# RX_Board.net
KiCad netlist of a schematic drawn in Altium Designer
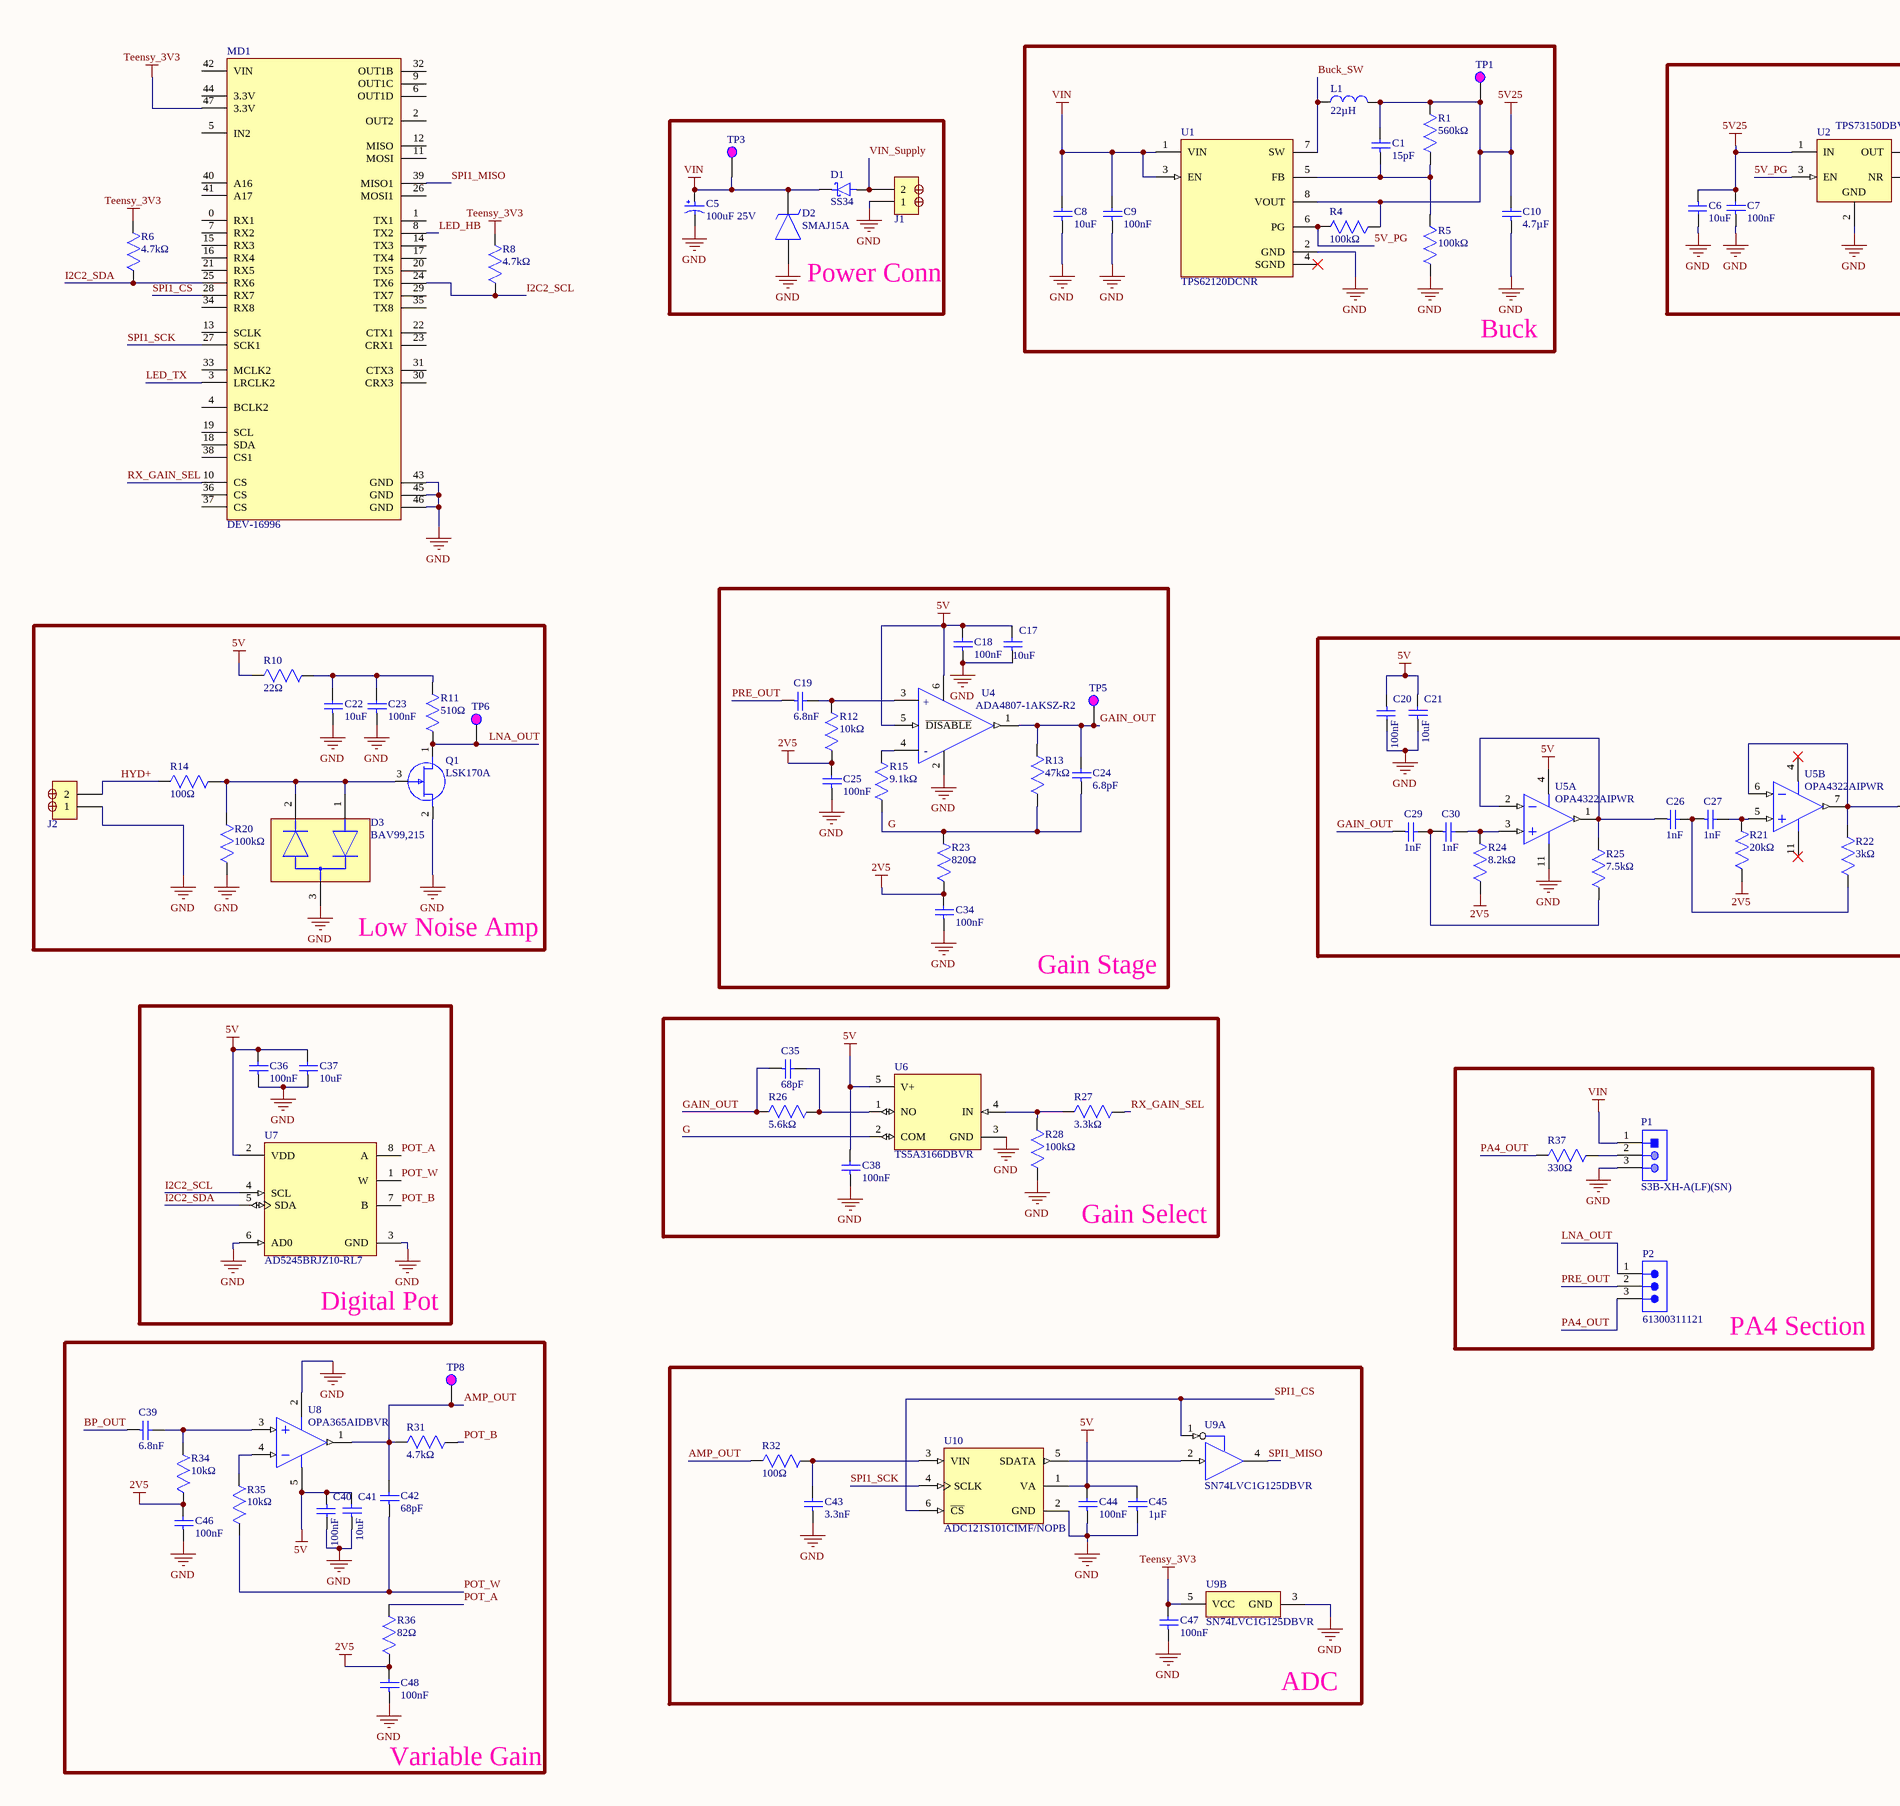
[diagram p0: RX_Board.SchDoc, left]
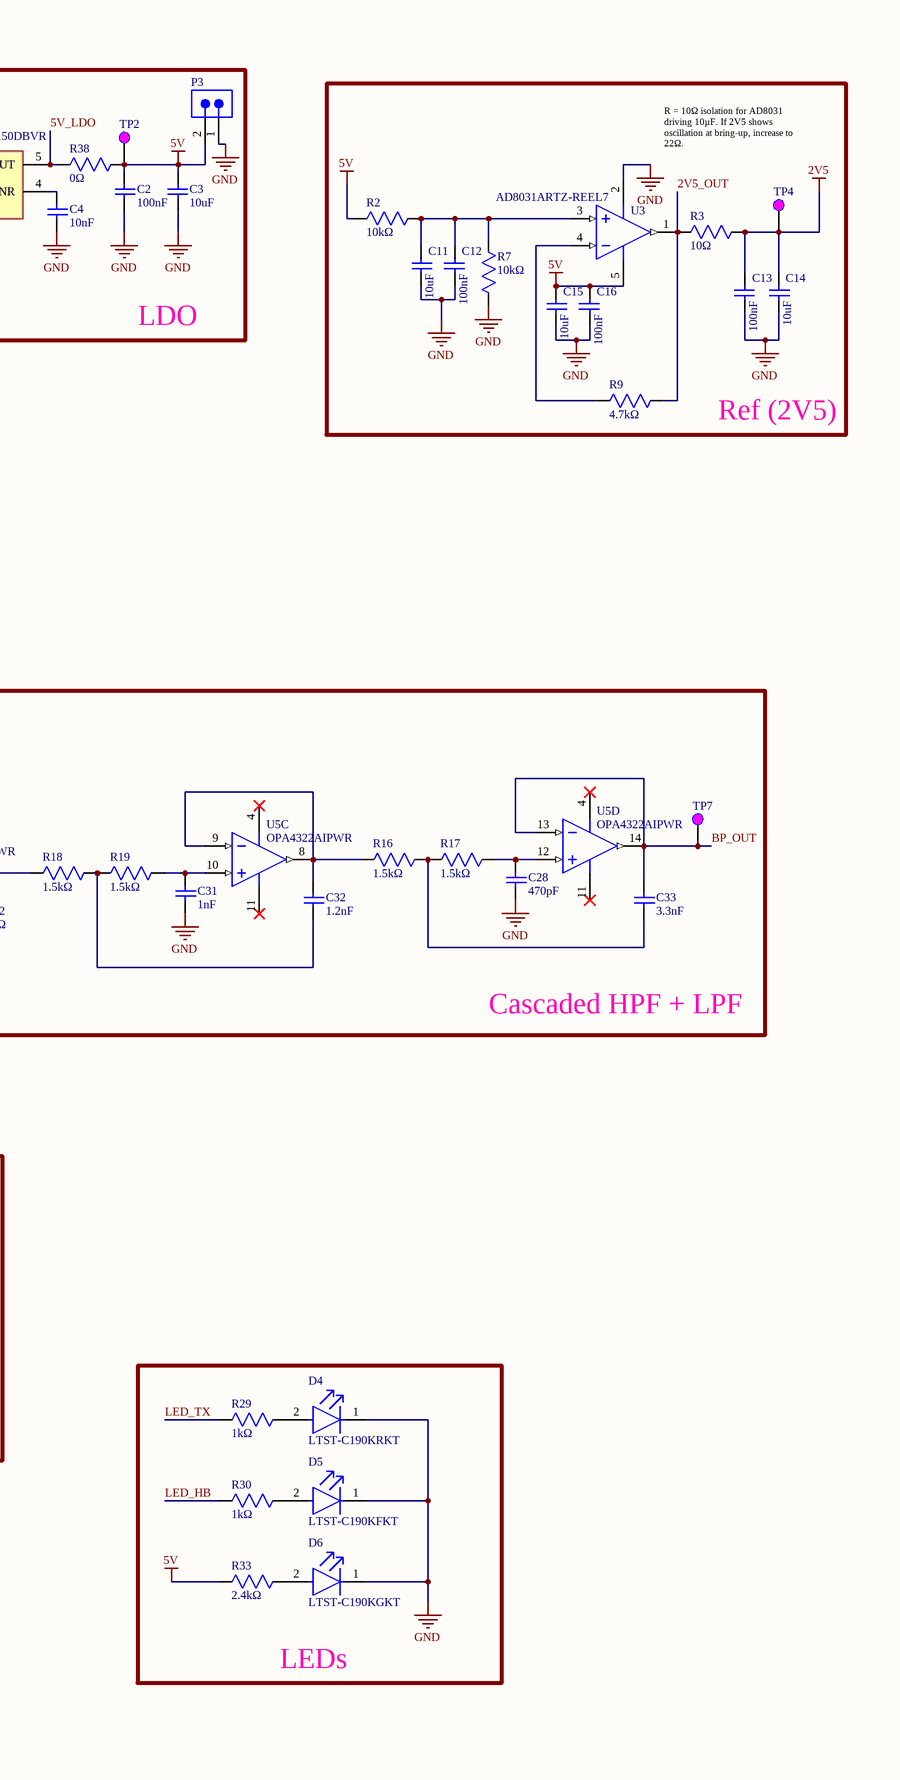
[diagram p1: RX_Board.SchDoc, right]

(export (version "E")
  (design (tool "Eeschema 10.0.6"))
  (components
    (comp (ref "C1")
      (value "15pF")
      (footprint "CAP_0603")
      (description "Multilayer Ceramic Capacitor, 15 pF, 50 V, ± 5%, C0G (NP0), 0603 [1608 Metric]")
      (fields
        (field (name "MANUFACTURER") "Samsung Electro-Mechanics")
        (field (name "MANUFACTURER PART NUMBER") "CL10C150JB8NNNC")
      )
      (libsource (lib "Custom_UAM_Parts") (part "CL10C150JB8NNNC"))
    )
    (comp (ref "C2")
      (value "100nF")
      (footprint "CAP_0603")
      (description "Multilayer Ceramic Capacitor, CC Series, 0.1 - F, - 10%, X7R, 50 V, 0603 [1608 Metric]")
      (fields
        (field (name "MANUFACTURER") "Yageo Group")
        (field (name "MANUFACTURER PART NUMBER") "CC0603KRX7R9BB104")
      )
      (libsource (lib "Custom_UAM_Parts") (part "CC0603KRX7R9BB104"))
    )
    (comp (ref "C3")
      (value "10uF")
      (footprint "CAP_0603")
      (description "25V 10uF X5R ±20% 0603 Multilayer Ceramic Capacitors MLCC - SMD/SMT ROHS")
      (fields
        (field (name "MANUFACTURER") "Samsung Electro-Mechanics")
        (field (name "MANUFACTURER PART NUMBER") "CL10A106MA8NRNC")
      )
      (libsource (lib "Custom_UAM_Parts") (part "CL10A106MA8NRNC"))
    )
    (comp (ref "C4")
      (value "10nF")
      (footprint "CAP_0603")
      (description "Surface Mount Ceramic Multilayer Capacitor 0.01uF 5% X7R 50V 0603 Paper T/R")
      (fields
        (field (name "MANUFACTURER") "Yageo Group")
        (field (name "MANUFACTURER PART NUMBER") "CC0603JRX7R9BB103")
      )
      (libsource (lib "Custom_UAM_Parts") (part "CC0603JRX7R9BB103"))
    )
    (comp (ref "C5")
      (value "100uF 25V")
      (footprint "SamacSys:CAPAE660X800N")
      (description "Capacitor Polarised")
      (fields
        (field (name "MANUFACTURER_PART_NUMBER") "RVT1E101M0607")
        (field (name "JLCPCB PART NUMBER") "C72477")
      )
      (libsource (lib "Custom_UAM_Parts") (part "RVT1E101M0607"))
    )
    (comp (ref "C6")
      (value "10uF")
      (footprint "CAP_0603")
      (description "25V 10uF X5R ±20% 0603 Multilayer Ceramic Capacitors MLCC - SMD/SMT ROHS")
      (fields
        (field (name "MANUFACTURER") "Samsung Electro-Mechanics")
        (field (name "MANUFACTURER PART NUMBER") "CL10A106MA8NRNC")
      )
      (libsource (lib "Custom_UAM_Parts") (part "CL10A106MA8NRNC"))
    )
    (comp (ref "C7")
      (value "100nF")
      (footprint "CAP_0603")
      (description "Multilayer Ceramic Capacitor, CC Series, 0.1 - F, - 10%, X7R, 50 V, 0603 [1608 Metric]")
      (fields
        (field (name "MANUFACTURER") "Yageo Group")
        (field (name "MANUFACTURER PART NUMBER") "CC0603KRX7R9BB104")
      )
      (libsource (lib "Custom_UAM_Parts") (part "CC0603KRX7R9BB104"))
    )
    (comp (ref "C8")
      (value "10uF")
      (footprint "CAP_0603")
      (description "25V 10uF X5R ±20% 0603 Multilayer Ceramic Capacitors MLCC - SMD/SMT ROHS")
      (fields
        (field (name "MANUFACTURER") "Samsung Electro-Mechanics")
        (field (name "MANUFACTURER PART NUMBER") "CL10A106MA8NRNC")
      )
      (libsource (lib "Custom_UAM_Parts") (part "CL10A106MA8NRNC"))
    )
    (comp (ref "C9")
      (value "100nF")
      (footprint "CAP_0603")
      (description "Multilayer Ceramic Capacitor, CC Series, 0.1 - F, - 10%, X7R, 50 V, 0603 [1608 Metric]")
      (fields
        (field (name "MANUFACTURER") "Yageo Group")
        (field (name "MANUFACTURER PART NUMBER") "CC0603KRX7R9BB104")
      )
      (libsource (lib "Custom_UAM_Parts") (part "CC0603KRX7R9BB104"))
    )
    (comp (ref "C10")
      (value "4.7µF")
      (footprint "CAP_0603")
      (description "25V 4.7uF X5R 卤10% 0603 Multilayer Ceramic Capacitors MLCC - SMD/SMT ROHS")
      (fields
        (field (name "MANUFACTURER") "Samsung Electro-Mechanics")
        (field (name "MANUFACTURER PART NUMBER") "CL10A475KA8NQNC")
      )
      (libsource (lib "Custom_UAM_Parts") (part "CL10A475KA8NQNC"))
    )
    (comp (ref "C11")
      (value "10uF")
      (footprint "CAP_0603")
      (description "25V 10uF X5R ±20% 0603 Multilayer Ceramic Capacitors MLCC - SMD/SMT ROHS")
      (fields
        (field (name "MANUFACTURER") "Samsung Electro-Mechanics")
        (field (name "MANUFACTURER PART NUMBER") "CL10A106MA8NRNC")
      )
      (libsource (lib "Custom_UAM_Parts") (part "CL10A106MA8NRNC"))
    )
    (comp (ref "C12")
      (value "100nF")
      (footprint "CAP_0603")
      (description "Multilayer Ceramic Capacitor, CC Series, 0.1 - F, - 10%, X7R, 50 V, 0603 [1608 Metric]")
      (fields
        (field (name "MANUFACTURER") "Yageo Group")
        (field (name "MANUFACTURER PART NUMBER") "CC0603KRX7R9BB104")
      )
      (libsource (lib "Custom_UAM_Parts") (part "CC0603KRX7R9BB104"))
    )
    (comp (ref "C13")
      (value "100nF")
      (footprint "CAP_0603")
      (description "Multilayer Ceramic Capacitor, CC Series, 0.1 - F, - 10%, X7R, 50 V, 0603 [1608 Metric]")
      (fields
        (field (name "MANUFACTURER") "Yageo Group")
        (field (name "MANUFACTURER PART NUMBER") "CC0603KRX7R9BB104")
      )
      (libsource (lib "Custom_UAM_Parts") (part "CC0603KRX7R9BB104"))
    )
    (comp (ref "C14")
      (value "10uF")
      (footprint "CAP_0603")
      (description "25V 10uF X5R ±20% 0603 Multilayer Ceramic Capacitors MLCC - SMD/SMT ROHS")
      (fields
        (field (name "MANUFACTURER") "Samsung Electro-Mechanics")
        (field (name "MANUFACTURER PART NUMBER") "CL10A106MA8NRNC")
      )
      (libsource (lib "Custom_UAM_Parts") (part "CL10A106MA8NRNC"))
    )
    (comp (ref "C15")
      (value "10uF")
      (footprint "CAP_0603")
      (description "25V 10uF X5R ±20% 0603 Multilayer Ceramic Capacitors MLCC - SMD/SMT ROHS")
      (fields
        (field (name "MANUFACTURER") "Samsung Electro-Mechanics")
        (field (name "MANUFACTURER PART NUMBER") "CL10A106MA8NRNC")
      )
      (libsource (lib "Custom_UAM_Parts") (part "CL10A106MA8NRNC"))
    )
    (comp (ref "C16")
      (value "100nF")
      (footprint "CAP_0603")
      (description "Multilayer Ceramic Capacitor, CC Series, 0.1 - F, - 10%, X7R, 50 V, 0603 [1608 Metric]")
      (fields
        (field (name "MANUFACTURER") "Yageo Group")
        (field (name "MANUFACTURER PART NUMBER") "CC0603KRX7R9BB104")
      )
      (libsource (lib "Custom_UAM_Parts") (part "CC0603KRX7R9BB104"))
    )
    (comp (ref "C17")
      (value "10uF")
      (footprint "CAP_0603")
      (description "25V 10uF X5R ±20% 0603 Multilayer Ceramic Capacitors MLCC - SMD/SMT ROHS")
      (fields
        (field (name "MANUFACTURER") "Samsung Electro-Mechanics")
        (field (name "MANUFACTURER PART NUMBER") "CL10A106MA8NRNC")
      )
      (libsource (lib "Custom_UAM_Parts") (part "CL10A106MA8NRNC"))
    )
    (comp (ref "C18")
      (value "100nF")
      (footprint "CAP_0603")
      (description "Multilayer Ceramic Capacitor, CC Series, 0.1 - F, - 10%, X7R, 50 V, 0603 [1608 Metric]")
      (fields
        (field (name "MANUFACTURER") "Yageo Group")
        (field (name "MANUFACTURER PART NUMBER") "CC0603KRX7R9BB104")
      )
      (libsource (lib "Custom_UAM_Parts") (part "CC0603KRX7R9BB104"))
    )
    (comp (ref "C19")
      (value "6.8nF")
      (footprint "CAP_0603")
      (description "Surface Mount Ceramic Multilayer Capacitor 0.0068uF 10% X7R 50V 0603 Paper T/R")
      (fields
        (field (name "MANUFACTURER") "Yageo Group")
        (field (name "MANUFACTURER PART NUMBER") "CC0603KRX7R9BB682")
      )
      (libsource (lib "Custom_UAM_Parts") (part "CC0603KRX7R9BB682"))
    )
    (comp (ref "C20")
      (value "100nF")
      (footprint "CAP_0603")
      (description "Multilayer Ceramic Capacitor, CC Series, 0.1 - F, - 10%, X7R, 50 V, 0603 [1608 Metric]")
      (fields
        (field (name "MANUFACTURER") "Yageo Group")
        (field (name "MANUFACTURER PART NUMBER") "CC0603KRX7R9BB104")
      )
      (libsource (lib "Custom_UAM_Parts") (part "CC0603KRX7R9BB104"))
    )
    (comp (ref "C21")
      (value "10uF")
      (footprint "CAP_0603")
      (description "25V 10uF X5R ±20% 0603 Multilayer Ceramic Capacitors MLCC - SMD/SMT ROHS")
      (fields
        (field (name "MANUFACTURER") "Samsung Electro-Mechanics")
        (field (name "MANUFACTURER PART NUMBER") "CL10A106MA8NRNC")
      )
      (libsource (lib "Custom_UAM_Parts") (part "CL10A106MA8NRNC"))
    )
    (comp (ref "C22")
      (value "10uF")
      (footprint "CAP_0603")
      (description "25V 10uF X5R ±20% 0603 Multilayer Ceramic Capacitors MLCC - SMD/SMT ROHS")
      (fields
        (field (name "MANUFACTURER") "Samsung Electro-Mechanics")
        (field (name "MANUFACTURER PART NUMBER") "CL10A106MA8NRNC")
      )
      (libsource (lib "Custom_UAM_Parts") (part "CL10A106MA8NRNC"))
    )
    (comp (ref "C23")
      (value "100nF")
      (footprint "CAP_0603")
      (description "Multilayer Ceramic Capacitor, CC Series, 0.1 - F, - 10%, X7R, 50 V, 0603 [1608 Metric]")
      (fields
        (field (name "MANUFACTURER") "Yageo Group")
        (field (name "MANUFACTURER PART NUMBER") "CC0603KRX7R9BB104")
      )
      (libsource (lib "Custom_UAM_Parts") (part "CC0603KRX7R9BB104"))
    )
    (comp (ref "C24")
      (value "6.8pF")
      (footprint "CAP_0603")
      (description "Surface Mount Ceramic Multilayer Capacitor 6.8pF 0.25pF C0G 50V 0603 Paper T/R")
      (fields
        (field (name "MANUFACTURER") "Yageo Group")
        (field (name "MANUFACTURER PART NUMBER") "CC0603CRNPO9BN6R8")
      )
      (libsource (lib "Custom_UAM_Parts") (part "CC0603CRNPO9BN6R8"))
    )
    (comp (ref "C25")
      (value "100nF")
      (footprint "CAP_0603")
      (description "Multilayer Ceramic Capacitor, CC Series, 0.1 - F, - 10%, X7R, 50 V, 0603 [1608 Metric]")
      (fields
        (field (name "MANUFACTURER") "Yageo Group")
        (field (name "MANUFACTURER PART NUMBER") "CC0603KRX7R9BB104")
      )
      (libsource (lib "Custom_UAM_Parts") (part "CC0603KRX7R9BB104"))
    )
    (comp (ref "C26")
      (value "1nF")
      (footprint "CAP_0603")
      (description "50V 1nF NP0 ±5% 0603 Multilayer Ceramic Capacitors MLCC - SMD/SMT ROHS")
      (fields
        (field (name "MANUFACTURER") "Yageo Group")
        (field (name "MANUFACTURER PART NUMBER") "CC0603JRNPO9BN102")
      )
      (libsource (lib "Custom_UAM_Parts") (part "CC0603JRNPO9BN102"))
    )
    (comp (ref "C27")
      (value "1nF")
      (footprint "CAP_0603")
      (description "50V 1nF NP0 ±5% 0603 Multilayer Ceramic Capacitors MLCC - SMD/SMT ROHS")
      (fields
        (field (name "MANUFACTURER") "Yageo Group")
        (field (name "MANUFACTURER PART NUMBER") "CC0603JRNPO9BN102")
      )
      (libsource (lib "Custom_UAM_Parts") (part "CC0603JRNPO9BN102"))
    )
    (comp (ref "C28")
      (value "470pF")
      (footprint "CAP_0603")
      (description "50V 470pF NP0 ±1% 0603 Multilayer Ceramic Capacitors MLCC - SMD/SMT ROHS")
      (fields
        (field (name "MANUFACTURER") "Yageo Group")
        (field (name "MANUFACTURER PART NUMBER") "CC0603FRNPO9BN471")
      )
      (libsource (lib "Custom_UAM_Parts") (part "CC0603FRNPO9BN471"))
    )
    (comp (ref "C29")
      (value "1nF")
      (footprint "CAP_0603")
      (description "50V 1nF NP0 ±5% 0603 Multilayer Ceramic Capacitors MLCC - SMD/SMT ROHS")
      (fields
        (field (name "MANUFACTURER") "Yageo Group")
        (field (name "MANUFACTURER PART NUMBER") "CC0603JRNPO9BN102")
      )
      (libsource (lib "Custom_UAM_Parts") (part "CC0603JRNPO9BN102"))
    )
    (comp (ref "C30")
      (value "1nF")
      (footprint "CAP_0603")
      (description "50V 1nF NP0 ±5% 0603 Multilayer Ceramic Capacitors MLCC - SMD/SMT ROHS")
      (fields
        (field (name "MANUFACTURER") "Yageo Group")
        (field (name "MANUFACTURER PART NUMBER") "CC0603JRNPO9BN102")
      )
      (libsource (lib "Custom_UAM_Parts") (part "CC0603JRNPO9BN102"))
    )
    (comp (ref "C31")
      (value "1nF")
      (footprint "CAP_0603")
      (description "50V 1nF NP0 ±5% 0603 Multilayer Ceramic Capacitors MLCC - SMD/SMT ROHS")
      (fields
        (field (name "MANUFACTURER") "Yageo Group")
        (field (name "MANUFACTURER PART NUMBER") "CC0603JRNPO9BN102")
      )
      (libsource (lib "Custom_UAM_Parts") (part "CC0603JRNPO9BN102"))
    )
    (comp (ref "C32")
      (value "1.2nF")
      (footprint "CAP_0603")
      (description "50V 1.2nF NP0 ±5% 0603 Multilayer Ceramic Capacitors MLCC - SMD/SMT ROHS")
      (fields
        (field (name "MANUFACTURER") "Yageo Group")
        (field (name "MANUFACTURER PART NUMBER") "CC0603JRNPO9BN122")
      )
      (libsource (lib "Custom_UAM_Parts") (part "CC0603JRNPO9BN122"))
    )
    (comp (ref "C33")
      (value "3.3nF")
      (footprint "CAP_0603")
      (description "50V 3.3nF NP0 ±5% 0603 Multilayer Ceramic Capacitors MLCC - SMD/SMT ROHS")
      (fields
        (field (name "MANUFACTURER") "Yageo Group")
        (field (name "MANUFACTURER PART NUMBER") "CC0603JRNPO9BN332")
      )
      (libsource (lib "Custom_UAM_Parts") (part "CC0603JRNPO9BN332"))
    )
    (comp (ref "C34")
      (value "100nF")
      (footprint "CAP_0603")
      (description "Multilayer Ceramic Capacitor, CC Series, 0.1 - F, - 10%, X7R, 50 V, 0603 [1608 Metric]")
      (fields
        (field (name "MANUFACTURER") "Yageo Group")
        (field (name "MANUFACTURER PART NUMBER") "CC0603KRX7R9BB104")
      )
      (libsource (lib "Custom_UAM_Parts") (part "CC0603KRX7R9BB104"))
    )
    (comp (ref "C35")
      (value "68pF")
      (footprint "CAP_0603")
      (description "Multilayer Ceramic Capacitor, 68 pF, 50 V, ± 5%, C0G (NP0), 0603 [1608 Metric]")
      (fields
        (field (name "MANUFACTURER") "Yageo Group")
        (field (name "MANUFACTURER PART NUMBER") "CC0603JRNPO9BN680")
      )
      (libsource (lib "Custom_UAM_Parts") (part "CC0603JRNPO9BN680"))
    )
    (comp (ref "C36")
      (value "100nF")
      (footprint "CAP_0603")
      (description "Multilayer Ceramic Capacitor, CC Series, 0.1 - F, - 10%, X7R, 50 V, 0603 [1608 Metric]")
      (fields
        (field (name "MANUFACTURER") "Yageo Group")
        (field (name "MANUFACTURER PART NUMBER") "CC0603KRX7R9BB104")
      )
      (libsource (lib "Custom_UAM_Parts") (part "CC0603KRX7R9BB104"))
    )
    (comp (ref "C37")
      (value "10uF")
      (footprint "CAP_0603")
      (description "25V 10uF X5R ±20% 0603 Multilayer Ceramic Capacitors MLCC - SMD/SMT ROHS")
      (fields
        (field (name "MANUFACTURER") "Samsung Electro-Mechanics")
        (field (name "MANUFACTURER PART NUMBER") "CL10A106MA8NRNC")
      )
      (libsource (lib "Custom_UAM_Parts") (part "CL10A106MA8NRNC"))
    )
    (comp (ref "C38")
      (value "100nF")
      (footprint "CAP_0603")
      (description "Multilayer Ceramic Capacitor, CC Series, 0.1 - F, - 10%, X7R, 50 V, 0603 [1608 Metric]")
      (fields
        (field (name "MANUFACTURER") "Yageo Group")
        (field (name "MANUFACTURER PART NUMBER") "CC0603KRX7R9BB104")
      )
      (libsource (lib "Custom_UAM_Parts") (part "CC0603KRX7R9BB104"))
    )
    (comp (ref "C39")
      (value "6.8nF")
      (footprint "CAP_0603")
      (description "Surface Mount Ceramic Multilayer Capacitor 0.0068uF 10% X7R 50V 0603 Paper T/R")
      (fields
        (field (name "MANUFACTURER") "Yageo Group")
        (field (name "MANUFACTURER PART NUMBER") "CC0603KRX7R9BB682")
      )
      (libsource (lib "Custom_UAM_Parts") (part "CC0603KRX7R9BB682"))
    )
    (comp (ref "C40")
      (value "100nF")
      (footprint "CAP_0603")
      (description "Multilayer Ceramic Capacitor, CC Series, 0.1 - F, - 10%, X7R, 50 V, 0603 [1608 Metric]")
      (fields
        (field (name "MANUFACTURER") "Yageo Group")
        (field (name "MANUFACTURER PART NUMBER") "CC0603KRX7R9BB104")
      )
      (libsource (lib "Custom_UAM_Parts") (part "CC0603KRX7R9BB104"))
    )
    (comp (ref "C41")
      (value "10uF")
      (footprint "CAP_0603")
      (description "25V 10uF X5R ±20% 0603 Multilayer Ceramic Capacitors MLCC - SMD/SMT ROHS")
      (fields
        (field (name "MANUFACTURER") "Samsung Electro-Mechanics")
        (field (name "MANUFACTURER PART NUMBER") "CL10A106MA8NRNC")
      )
      (libsource (lib "Custom_UAM_Parts") (part "CL10A106MA8NRNC"))
    )
    (comp (ref "C42")
      (value "68pF")
      (footprint "CAP_0603")
      (description "Multilayer Ceramic Capacitor, 68 pF, 50 V, ± 5%, C0G (NP0), 0603 [1608 Metric]")
      (fields
        (field (name "MANUFACTURER") "Yageo Group")
        (field (name "MANUFACTURER PART NUMBER") "CC0603JRNPO9BN680")
      )
      (libsource (lib "Custom_UAM_Parts") (part "CC0603JRNPO9BN680"))
    )
    (comp (ref "C43")
      (value "3.3nF")
      (footprint "CAP_0603")
      (description "50V 3.3nF NP0 ±5% 0603 Multilayer Ceramic Capacitors MLCC - SMD/SMT ROHS")
      (fields
        (field (name "MANUFACTURER") "Yageo Group")
        (field (name "MANUFACTURER PART NUMBER") "CC0603JRNPO9BN332")
      )
      (libsource (lib "Custom_UAM_Parts") (part "CC0603JRNPO9BN332"))
    )
    (comp (ref "C44")
      (value "100nF")
      (footprint "CAP_0603")
      (description "Multilayer Ceramic Capacitor, CC Series, 0.1 - F, - 10%, X7R, 50 V, 0603 [1608 Metric]")
      (fields
        (field (name "MANUFACTURER") "Yageo Group")
        (field (name "MANUFACTURER PART NUMBER") "CC0603KRX7R9BB104")
      )
      (libsource (lib "Custom_UAM_Parts") (part "CC0603KRX7R9BB104"))
    )
    (comp (ref "C45")
      (value "1µF")
      (footprint "CAP_0603")
      (description "MLCC - 0603 50 V X7R 1 uF 10 % Multilayer Ceramic Capacitor")
      (fields
        (field (name "MANUFACTURER") "Samsung Electro-Mechanics")
        (field (name "MANUFACTURER PART NUMBER") "CL10B105KB8NQNC")
      )
      (libsource (lib "Custom_UAM_Parts") (part "CL10B105KB8NQNC"))
    )
    (comp (ref "C46")
      (value "100nF")
      (footprint "CAP_0603")
      (description "Multilayer Ceramic Capacitor, CC Series, 0.1 - F, - 10%, X7R, 50 V, 0603 [1608 Metric]")
      (fields
        (field (name "MANUFACTURER") "Yageo Group")
        (field (name "MANUFACTURER PART NUMBER") "CC0603KRX7R9BB104")
      )
      (libsource (lib "Custom_UAM_Parts") (part "CC0603KRX7R9BB104"))
    )
    (comp (ref "C47")
      (value "100nF")
      (footprint "CAP_0603")
      (description "Multilayer Ceramic Capacitor, CC Series, 0.1 - F, - 10%, X7R, 50 V, 0603 [1608 Metric]")
      (fields
        (field (name "MANUFACTURER") "Yageo Group")
        (field (name "MANUFACTURER PART NUMBER") "CC0603KRX7R9BB104")
      )
      (libsource (lib "Custom_UAM_Parts") (part "CC0603KRX7R9BB104"))
    )
    (comp (ref "C48")
      (value "100nF")
      (footprint "CAP_0603")
      (description "Multilayer Ceramic Capacitor, CC Series, 0.1 - F, - 10%, X7R, 50 V, 0603 [1608 Metric]")
      (fields
        (field (name "MANUFACTURER") "Yageo Group")
        (field (name "MANUFACTURER PART NUMBER") "CC0603KRX7R9BB104")
      )
      (libsource (lib "Custom_UAM_Parts") (part "CC0603KRX7R9BB104"))
    )
    (comp (ref "D1")
      (value "SS34")
      (footprint "SS34")
      (description "-55℃~+125℃ 3A 40V 500uA@40V 550mV@3A Independent SMA(DO-214AC) Schottky Diodes ROHS")
      (fields (field (name "MANUFACTURER") "MDD") (field (name "JLCPCB PART NUMBER") "C8678"))
      (libsource (lib "Custom_UAM_Parts") (part "SS34"))
    )
    (comp (ref "D2")
      (value "SMAJ15A")
      (footprint "DIOM5026X229N")
      (description "SMAJ Series 24.4 V 400 W Surface Mount Uni-Directional TVS Diode - DO-214AC")
      (fields (field (name "MANUFACTURER") "Littelfuse") (field (name "JLCPCB PART NUMBER") "C148216"))
      (libsource (lib "Custom_UAM_Parts") (part "SMAJ15A"))
    )
    (comp (ref "D3")
      (value "BAV99,215")
      (footprint "FP-SOT23-MFG")
      (description "DIODE ARRAY GP 100V 215MA SOT23")
      (fields (field (name "JLCPCB PART NUMBER") "C2500"))
      (libsource (lib "Altium Content Vault") (part "86a7eb6839269cc1691df5cbdd99f75"))
    )
    (comp (ref "D4")
      (value "LTST-C190KRKT")
      (footprint "FP-LTST-C190KRKT-MFG")
      (description "LED RED CLEAR CHIP SMD")
      (fields (field (name "JLCPCB PART NUMBER") "C94869"))
      (libsource (lib "Altium Content Vault") (part "8706943c75ba83719d021d2fdc84c58"))
    )
    (comp (ref "D5")
      (value "LTST-C190KFKT")
      (footprint "FP-LTST-C190KFKT-MFG")
      (description "LED ORANGE CLEAR CHIP SMD")
      (fields (field (name "JLCPCB PART NUMBER") "C157740"))
      (libsource (lib "Altium Content Vault") (part "8706943c75ba83719d021d2fdc84c58"))
    )
    (comp (ref "D6")
      (value "LTST-C190KGKT")
      (footprint "FP-LTST-C190KGKT-MFG")
      (description "LED GREEN CLEAR CHIP SMD")
      (fields (field (name "JLCPCB PART NUMBER") "C125094"))
      (libsource (lib "Altium Content Vault") (part "8706943c75ba83719d021d2fdc84c58"))
    )
    (comp (ref "J1")
      (value "DB301V-3.5-2P-GN-S")
      (footprint "DB301V-3.5-2P-GN-S")
      (fields (field (name "JLCPCB PART NUMBER") "C695629"))
      (libsource (lib "") (part "DB301V-3.5-2P-GN-S_1"))
    )
    (comp (ref "J2")
      (value "DB301V-3.5-2P-GN-S")
      (footprint "DB301V-3.5-2P-GN-S")
      (fields (field (name "JLCPCB PART NUMBER") "C695629"))
      (libsource (lib "Custom_UAM_Parts") (part "DB301V-3.5-2P-GN-S"))
    )
    (comp (ref "L1")
      (value "22µH")
      (footprint "SWPA5040S100MT")
      (description "General Purpose Inductor, 22uH, 20%, 1 Element, Ferrite-Core, SMD, 2020")
      (fields
        (field (name "MANUFACTURER") "Sunlord")
        (field (name "MANUFACTURER PART NUMBER") "SWPA5040S220MT")
      )
      (libsource (lib "Custom_UAM_Parts") (part "SWPA5040S220MT"))
    )
    (comp (ref "MD1")
      (value "DEV-16996")
      (footprint "FP-DEV-16996-MFG")
      (description "TEENSY 4.1 (HEADERS)")
      (libsource (lib "Altium Content Vault") (part "080115a1ce54750370cf87ec145ee29"))
    )
    (comp (ref "P1")
      (value "S3B-XH-A(LF)(SN)")
      (footprint "JST-S3B-XH-A(LF)(SN)_V")
      (libsource (lib "Altium Content Vault") (part "CN-1P-M-R3"))
    )
    (comp (ref "P2")
      (value "61300311121")
      (footprint "61300311121")
      (description "THT Vertical Pin Header WR-PHD, Pitch 2.54 mm, Single Row, 3 pins")
      (libsource (lib "Altium Content Vault") (part "Header_Male_1R_03P"))
    )
    (comp (ref "P3")
      (value "61300211121")
      (footprint "61300211121")
      (description "THT Vertical Pin Header WR-PHD, Pitch 2.54 mm, Single Row, 2 pins")
      (libsource (lib "Altium Content Vault") (part "Header_Male_1R_02P"))
    )
    (comp (ref "Q1")
      (value "LSK170A")
      (footprint "SOT96P237X122-3N")
      (description "Jfet N-ch 40V 10MA SOT23-3")
      (fields
        (field (name "MANUFACTURER") "Linear Systems")
        (field (name "MANUFACTURER PART NUMBER") "LSK170A SOT-23 3L ROHS")
      )
      (libsource (lib "Custom_UAM_Parts") (part "LSK170A SOT-23 3L ROHS"))
    )
    (comp (ref "R1")
      (value "560kΩ")
      (footprint "RES_0603")
      (description "100mW Thin Film Resistor 75V ±25ppm/℃ ±0.1% 560kΩ 0603 Chip Resistor - Surface Mount ROHS")
      (fields
        (field (name "MANUFACTURER") "Yageo Group")
        (field (name "MANUFACTURER PART NUMBER") "RT0603BRD07560KL")
      )
      (libsource (lib "Custom_UAM_Parts") (part "RT0603BRD07560KL"))
    )
    (comp (ref "R2")
      (value "10kΩ")
      (footprint "RES_0603")
      (description "Res Thin Film 0603 10K Ohm 0.1% 1/10W ¦25ppm/¦C SMD Paper T/R")
      (fields
        (field (name "MANUFACTURER") "Yageo Group")
        (field (name "MANUFACTURER PART NUMBER") "RT0603BRD0710KL")
      )
      (libsource (lib "Custom_UAM_Parts") (part "RT0603BRD0710KL"))
    )
    (comp (ref "R3")
      (value "10Ω")
      (footprint "RES_0603")
      (description "Res Thick Film 0603 10 Ohm 1% 0.1W(1/10W) ±200ppm/C Pad SMD T/R")
      (fields
        (field (name "MANUFACTURER") "Royal Ohm")
        (field (name "MANUFACTURER PART NUMBER") "0603WAF100JT5E")
      )
      (libsource (lib "Custom_UAM_Parts") (part "0603WAF100JT5E"))
    )
    (comp (ref "R4")
      (value "100kΩ")
      (footprint "RES_0603")
      (description "100mW Thin Film Resistor 75V ±25ppm/℃ ±0.1% 100kΩ 0603 Chip Resistor - Surface Mount ROHS")
      (fields
        (field (name "MANUFACTURER") "Yageo Group")
        (field (name "MANUFACTURER PART NUMBER") "RT0603BRD07100KL")
      )
      (libsource (lib "Custom_UAM_Parts") (part "RT0603BRD07100KL"))
    )
    (comp (ref "R5")
      (value "100kΩ")
      (footprint "RES_0603")
      (description "100mW Thin Film Resistor 75V ±25ppm/℃ ±0.1% 100kΩ 0603 Chip Resistor - Surface Mount ROHS")
      (fields
        (field (name "MANUFACTURER") "Yageo Group")
        (field (name "MANUFACTURER PART NUMBER") "RT0603BRD07100KL")
      )
      (libsource (lib "Custom_UAM_Parts") (part "RT0603BRD07100KL"))
    )
    (comp (ref "R6")
      (value "4.7kΩ")
      (footprint "RES_0603")
      (description "Yageo RC0603FR-074K7L Resistor 0603 SMD 4.7k Ohm 1% 100mW Thick Film")
      (fields
        (field (name "MANUFACTURER") "Yageo Group")
        (field (name "MANUFACTURER PART NUMBER") "RC0603FR-074K7L")
      )
      (libsource (lib "Custom_UAM_Parts") (part "RC0603FR-074K7L"))
    )
    (comp (ref "R7")
      (value "10kΩ")
      (footprint "RES_0603")
      (description "Res Thin Film 0603 10K Ohm 0.1% 1/10W ¦25ppm/¦C SMD Paper T/R")
      (fields
        (field (name "MANUFACTURER") "Yageo Group")
        (field (name "MANUFACTURER PART NUMBER") "RT0603BRD0710KL")
      )
      (libsource (lib "Custom_UAM_Parts") (part "RT0603BRD0710KL"))
    )
    (comp (ref "R8")
      (value "4.7kΩ")
      (footprint "RES_0603")
      (description "Yageo RC0603FR-074K7L Resistor 0603 SMD 4.7k Ohm 1% 100mW Thick Film")
      (fields
        (field (name "MANUFACTURER") "Yageo Group")
        (field (name "MANUFACTURER PART NUMBER") "RC0603FR-074K7L")
      )
      (libsource (lib "Custom_UAM_Parts") (part "RC0603FR-074K7L"))
    )
    (comp (ref "R9")
      (value "4.7kΩ")
      (footprint "RES_0603")
      (description "Yageo RC0603FR-074K7L Resistor 0603 SMD 4.7k Ohm 1% 100mW Thick Film")
      (fields
        (field (name "MANUFACTURER") "Yageo Group")
        (field (name "MANUFACTURER PART NUMBER") "RC0603FR-074K7L")
      )
      (libsource (lib "Custom_UAM_Parts") (part "RC0603FR-074K7L"))
    )
    (comp (ref "R10")
      (value "22Ω")
      (footprint "RES_0603")
      (description "Thick Film Resistors - SMD RMC 0603 1/10W 1% T/R-5000")
      (fields
        (field (name "MANUFACTURER") "Royal Ohm")
        (field (name "MANUFACTURER PART NUMBER") "0603WAF220JT5E")
      )
      (libsource (lib "Custom_UAM_Parts") (part "0603WAF220JT5E"))
    )
    (comp (ref "R11")
      (value "510Ω")
      (footprint "RES_0603")
      (description "Res Thick Film 0603 510 Ohm 1% 0.1W(1/10W) ±100ppm/C Pad SMD T/R")
      (fields
        (field (name "MANUFACTURER") "Royal Ohm")
        (field (name "MANUFACTURER PART NUMBER") "0603WAF5100T5E")
      )
      (libsource (lib "Custom_UAM_Parts") (part "0603WAF5100T5E"))
    )
    (comp (ref "R12")
      (value "10kΩ")
      (footprint "RES_0603")
      (description "Res Thin Film 0603 10K Ohm 0.1% 1/10W ¦25ppm/¦C SMD Paper T/R")
      (fields
        (field (name "MANUFACTURER") "Yageo Group")
        (field (name "MANUFACTURER PART NUMBER") "RT0603BRD0710KL")
      )
      (libsource (lib "Custom_UAM_Parts") (part "RT0603BRD0710KL"))
    )
    (comp (ref "R13")
      (value "47kΩ")
      (footprint "RES_0603")
      (description "Res Thick Film 0603 47K Ohm 1% 0.1W(1/10W) ±100ppm/C Pad SMD T/R")
      (fields
        (field (name "MANUFACTURER") "Royal Ohm")
        (field (name "MANUFACTURER PART NUMBER") "0603WAF4702T5E")
      )
      (libsource (lib "Custom_UAM_Parts") (part "0603WAF4702T5E"))
    )
    (comp (ref "R14")
      (value "100Ω")
      (footprint "RES_0603")
      (description "Res Thick Film 0603 100 Ohm 1% 0.1W(1/10W) ±200ppm/C Pad SMD T/R")
      (fields
        (field (name "MANUFACTURER") "Royal Ohm")
        (field (name "MANUFACTURER PART NUMBER") "0603WAF1000T5E")
      )
      (libsource (lib "Custom_UAM_Parts") (part "0603WAF1000T5E"))
    )
    (comp (ref "R15")
      (value "9.1kΩ")
      (footprint "RES_0603")
      (description "100mW Thick Film Resistors 75V ±100ppm/℃ ±1% 9.1kΩ 0603 Chip Resistor - Surface Mount ROHS")
      (fields
        (field (name "MANUFACTURER") "Royal Ohm")
        (field (name "MANUFACTURER PART NUMBER") "0603WAF9101T5E")
      )
      (libsource (lib "Custom_UAM_Parts") (part "0603WAF9101T5E"))
    )
    (comp (ref "R16")
      (value "1.5kΩ")
      (footprint "RES_0603")
      (description "Res Thick Film 0603 1.5K Ohm 1% 0.1W(1/10W) ±100ppm/C Pad SMD T/R")
      (fields
        (field (name "MANUFACTURER") "Royal Ohm")
        (field (name "MANUFACTURER PART NUMBER") "0603WAF1501T5E")
      )
      (libsource (lib "Custom_UAM_Parts") (part "0603WAF1501T5E"))
    )
    (comp (ref "R17")
      (value "1.5kΩ")
      (footprint "RES_0603")
      (description "Res Thick Film 0603 1.5K Ohm 1% 0.1W(1/10W) ±100ppm/C Pad SMD T/R")
      (fields
        (field (name "MANUFACTURER") "Royal Ohm")
        (field (name "MANUFACTURER PART NUMBER") "0603WAF1501T5E")
      )
      (libsource (lib "Custom_UAM_Parts") (part "0603WAF1501T5E"))
    )
    (comp (ref "R18")
      (value "1.5kΩ")
      (footprint "RES_0603")
      (description "Res Thick Film 0603 1.5K Ohm 1% 0.1W(1/10W) ±100ppm/C Pad SMD T/R")
      (fields
        (field (name "MANUFACTURER") "Royal Ohm")
        (field (name "MANUFACTURER PART NUMBER") "0603WAF1501T5E")
      )
      (libsource (lib "Custom_UAM_Parts") (part "0603WAF1501T5E"))
    )
    (comp (ref "R19")
      (value "1.5kΩ")
      (footprint "RES_0603")
      (description "Res Thick Film 0603 1.5K Ohm 1% 0.1W(1/10W) ±100ppm/C Pad SMD T/R")
      (fields
        (field (name "MANUFACTURER") "Royal Ohm")
        (field (name "MANUFACTURER PART NUMBER") "0603WAF1501T5E")
      )
      (libsource (lib "Custom_UAM_Parts") (part "0603WAF1501T5E"))
    )
    (comp (ref "R20")
      (value "100kΩ")
      (footprint "RES_0603")
      (description "100mW Thin Film Resistor 75V ±25ppm/℃ ±0.1% 100kΩ 0603 Chip Resistor - Surface Mount ROHS")
      (fields
        (field (name "MANUFACTURER") "Yageo Group")
        (field (name "MANUFACTURER PART NUMBER") "RT0603BRD07100KL")
      )
      (libsource (lib "Custom_UAM_Parts") (part "RT0603BRD07100KL"))
    )
    (comp (ref "R21")
      (value "20kΩ")
      (footprint "RES_0603")
      (description "100mW Thick Film Resistors 75V ±100ppm/℃ ±1% 20kΩ 0603 Chip Resistor - Surface Mount ROHS")
      (fields
        (field (name "MANUFACTURER") "Royal Ohm")
        (field (name "MANUFACTURER PART NUMBER") "0603WAF2002T5E")
      )
      (libsource (lib "Custom_UAM_Parts") (part "0603WAF2002T5E"))
    )
    (comp (ref "R22")
      (value "3kΩ")
      (footprint "RES_0603")
      (description "Thick Film Resistors - SMD RMC 0603 1/10W 1% T/R-5000")
      (fields
        (field (name "MANUFACTURER") "Royal Ohm")
        (field (name "MANUFACTURER PART NUMBER") "0603WAF3001T5E")
      )
      (libsource (lib "Custom_UAM_Parts") (part "0603WAF3001T5E"))
    )
    (comp (ref "R23")
      (value "820Ω")
      (footprint "RES_0603")
      (description "Thick Film Resistors - SMD RMC 0603 1/10W 1% T/R-5000")
      (fields
        (field (name "MANUFACTURER") "Royal Ohm")
        (field (name "MANUFACTURER PART NUMBER") "0603WAF8200T5E")
      )
      (libsource (lib "Custom_UAM_Parts") (part "0603WAF8200T5E"))
    )
    (comp (ref "R24")
      (value "8.2kΩ")
      (footprint "RES_0603")
      (description "Res Thick Film 0603 8.2K Ohm 1% 0.1W(1/10W) ±100ppm/C Pad SMD T/R")
      (fields
        (field (name "MANUFACTURER") "Royal Ohm")
        (field (name "MANUFACTURER PART NUMBER") "0603WAF8201T5E")
      )
      (libsource (lib "Custom_UAM_Parts") (part "0603WAF8201T5E"))
    )
    (comp (ref "R25")
      (value "7.5kΩ")
      (footprint "RES_0603")
      (fields
        (field (name "MANUFACTURER") "Royal Ohm")
        (field (name "MANUFACTURER PART NUMBER") "0603WAF7501T5E")
        (field (name "TOLERANCE") "1%")
      )
      (libsource (lib "Custom_UAM_Parts") (part "0603WAF7501T5E"))
    )
    (comp (ref "R26")
      (value "5.6kΩ")
      (footprint "RES_0603")
      (description "Res Thick Film 0603 5.6K Ohm 1% 0.1W(1/10W) ±100ppm/C Pad SMD T/R")
      (fields
        (field (name "MANUFACTURER") "Royal Ohm")
        (field (name "MANUFACTURER PART NUMBER") "0603WAF5601T5E")
      )
      (libsource (lib "Custom_UAM_Parts") (part "0603WAF5601T5E"))
    )
    (comp (ref "R27")
      (value "3.3kΩ")
      (footprint "RES_0603")
      (fields
        (field (name "MANUFACTURER") "Royal Ohm")
        (field (name "MANUFACTURER PART NUMBER") "0603WAF3301T5E")
        (field (name "TOLERANCE") "1%")
      )
      (libsource (lib "Custom_UAM_Parts") (part "0603WAF3301T5E"))
    )
    (comp (ref "R28")
      (value "100kΩ")
      (footprint "RES_0603")
      (description "100mW Thin Film Resistor 75V ±25ppm/℃ ±0.1% 100kΩ 0603 Chip Resistor - Surface Mount ROHS")
      (fields
        (field (name "MANUFACTURER") "Yageo Group")
        (field (name "MANUFACTURER PART NUMBER") "RT0603BRD07100KL")
      )
      (libsource (lib "Custom_UAM_Parts") (part "RT0603BRD07100KL"))
    )
    (comp (ref "R29")
      (value "1kΩ")
      (footprint "RES_0603")
      (description "Res Thick Film 0603 1K Ohm 1% 0.1W(1/10W) ±100ppm/C Pad SMD T/R")
      (fields
        (field (name "MANUFACTURER") "Royal Ohm")
        (field (name "MANUFACTURER PART NUMBER") "0603WAF1001T5E")
      )
      (libsource (lib "Custom_UAM_Parts") (part "0603WAF1001T5E"))
    )
    (comp (ref "R30")
      (value "1kΩ")
      (footprint "RES_0603")
      (description "Res Thick Film 0603 1K Ohm 1% 0.1W(1/10W) ±100ppm/C Pad SMD T/R")
      (fields
        (field (name "MANUFACTURER") "Royal Ohm")
        (field (name "MANUFACTURER PART NUMBER") "0603WAF1001T5E")
      )
      (libsource (lib "Custom_UAM_Parts") (part "0603WAF1001T5E"))
    )
    (comp (ref "R31")
      (value "4.7kΩ")
      (footprint "RES_0603")
      (description "Yageo RC0603FR-074K7L Resistor 0603 SMD 4.7k Ohm 1% 100mW Thick Film")
      (fields
        (field (name "MANUFACTURER") "Yageo Group")
        (field (name "MANUFACTURER PART NUMBER") "RC0603FR-074K7L")
      )
      (libsource (lib "Custom_UAM_Parts") (part "RC0603FR-074K7L"))
    )
    (comp (ref "R32")
      (value "100Ω")
      (footprint "RES_0603")
      (description "Res Thick Film 0603 100 Ohm 1% 0.1W(1/10W) ±200ppm/C Pad SMD T/R")
      (fields
        (field (name "MANUFACTURER") "Royal Ohm")
        (field (name "MANUFACTURER PART NUMBER") "0603WAF1000T5E")
      )
      (libsource (lib "Custom_UAM_Parts") (part "0603WAF1000T5E"))
    )
    (comp (ref "R33")
      (value "2.4kΩ")
      (footprint "RES_0603")
      (description "100mW Thick Film Resistors 75V ±100ppm/℃ ±1% 2.4kΩ 0603 Chip Resistor - Surface Mount ROHS")
      (fields
        (field (name "MANUFACTURER") "Royal Ohm")
        (field (name "MANUFACTURER PART NUMBER") "0603WAF2401T5E")
      )
      (libsource (lib "Custom_UAM_Parts") (part "0603WAF2401T5E"))
    )
    (comp (ref "R34")
      (value "10kΩ")
      (footprint "RES_0603")
      (description "Res Thin Film 0603 10K Ohm 0.1% 1/10W ¦25ppm/¦C SMD Paper T/R")
      (fields
        (field (name "MANUFACTURER") "Yageo Group")
        (field (name "MANUFACTURER PART NUMBER") "RT0603BRD0710KL")
      )
      (libsource (lib "Custom_UAM_Parts") (part "RT0603BRD0710KL"))
    )
    (comp (ref "R35")
      (value "10kΩ")
      (footprint "RES_0603")
      (description "Res Thin Film 0603 10K Ohm 0.1% 1/10W ¦25ppm/¦C SMD Paper T/R")
      (fields
        (field (name "MANUFACTURER") "Yageo Group")
        (field (name "MANUFACTURER PART NUMBER") "RT0603BRD0710KL")
      )
      (libsource (lib "Custom_UAM_Parts") (part "RT0603BRD0710KL"))
    )
    (comp (ref "R36")
      (value "82Ω")
      (footprint "RES_0603")
      (description "SMD Chip Resistor, 82 Ohm, ± 1%, 100 mW, 0603 [1608 Metric], Thick Film, General Purpose")
      (fields
        (field (name "MANUFACTURER") "Yageo Group")
        (field (name "MANUFACTURER PART NUMBER") "RC0603FR-0782RL")
      )
      (libsource (lib "Custom_UAM_Parts") (part "RC0603FR-0782RL"))
    )
    (comp (ref "R37")
      (value "330Ω")
      (footprint "RES_0603")
      (fields
        (field (name "MANUFACTURER") "Royal Ohm")
        (field (name "MANUFACTURER PART NUMBER") "0603WAF3300T5E")
        (field (name "TOLERANCE") "1%")
      )
      (libsource (lib "Custom_UAM_Parts") (part "0603WAF3300T5E"))
    )
    (comp (ref "R38")
      (value "0Ω")
      (footprint "RES_0603")
      (description "Zero Ohm Resistor, Jumper, 0603 [1608 Metric], Thick Film, 100 mW, 1 A, Surface Mount")
      (fields
        (field (name "MANUFACTURER") "Yageo Group")
        (field (name "MANUFACTURER PART NUMBER") "RC0603FR-070RL")
      )
      (libsource (lib "Custom_UAM_Parts") (part "RC0603FR-070RL"))
    )
    (comp (ref "TP1")
      (value "Test Point")
      (footprint "Test Point")
      (libsource (lib "Custom_UAM_Parts") (part "Test Point"))
    )
    (comp (ref "TP2")
      (value "Test Point")
      (footprint "Test Point")
      (libsource (lib "Custom_UAM_Parts") (part "Test Point"))
    )
    (comp (ref "TP3")
      (value "Test Point")
      (footprint "Test Point")
      (libsource (lib "Custom_UAM_Parts") (part "Test Point"))
    )
    (comp (ref "TP4")
      (value "Test Point")
      (footprint "Test Point")
      (libsource (lib "Custom_UAM_Parts") (part "Test Point"))
    )
    (comp (ref "TP5")
      (value "Test Point")
      (footprint "Test Point")
      (libsource (lib "Custom_UAM_Parts") (part "Test Point"))
    )
    (comp (ref "TP6")
      (value "Test Point")
      (footprint "Test Point")
      (libsource (lib "Custom_UAM_Parts") (part "Test Point"))
    )
    (comp (ref "TP7")
      (value "Test Point")
      (footprint "Test Point")
      (libsource (lib "Custom_UAM_Parts") (part "Test Point"))
    )
    (comp (ref "TP8")
      (value "Test Point")
      (footprint "Test Point")
      (libsource (lib "Custom_UAM_Parts") (part "Test Point"))
    )
    (comp (ref "U1")
      (value "TPS62120DCNR")
      (footprint "FP-DCN0008A-MFG")
      (description "IC REG BUCK ADJ 75MA SOT23-8")
      (libsource (lib "Altium Content Vault") (part "14865cc4e84ea28e7204c9f8caa9625"))
    )
    (comp (ref "U2")
      (value "TPS73150DBVR")
      (footprint "DBV0005A_N")
      (fields (field (name "MANUFACTURER") "Texas Instruments"))
      (libsource (lib "Altium Content Vault") (part "TI-TPS79NXX-YYSOT5"))
    )
    (comp (ref "U3")
      (value "AD8031ARTZ-REEL7")
      (footprint "ADI-RJ-5_L")
      (fields (field (name "MANUFACTURER") "Analog Devices") (field (name "GENERIC PART NUMBER") "AD8031"))
      (libsource (lib "Altium Content Vault") (part "ADI-AD80XX-5"))
    )
    (comp (ref "U4")
      (value "ADA4807-1AKSZ-R2")
      (footprint "FP-KS-6-IPC_C")
      (description "IC OPAMP VFB 1 CIRCUIT SC70-6")
      (fields
        (field (name "MANUFACTURER") "Analog Devices")
        (field (name "OCTOPART") "https://octopart.com/ada4807-1aksz-r2-analog+devices-52932031")
      )
      (libsource (lib "Altium Content Vault") (part "4985ff539af837c5b5b6b47cd6c0464"))
    )
    (comp (ref "U5")
      (value "OPA4322AIPWR")
      (footprint "PW0014A_N")
      (fields (field (name "MANUFACTURER") "Texas Instruments"))
      (libsource (lib "Altium Content Vault") (part "TI-OPA16X4_4XXX-14"))
    )
    (comp (ref "U6")
      (value "TS5A3166DBVR")
      (footprint "FP-DBV0005A-MFG")
      (description "IC SWITCH SPST SOT23-5")
      (fields
        (field (name "MANUFACTURER") "Texas Instruments")
        (field (name "OCTOPART") "https://octopart.com/ts5a3166dbvr-texas+instruments-512330")
      )
      (libsource (lib "Altium Content Vault") (part "821cfbbac4e375bc87997324a3db2e8"))
    )
    (comp (ref "U7")
      (value "AD5245BRJZ10-RL7")
      (footprint "FP-RJ-8-IPC_B")
      (description "IC DGT POT 10KOHM 256TAP SOT23-8")
      (fields (field (name "TOLERANCE") "30%") (field (name "JLCPCB PART NUMBER") "C144256"))
      (libsource (lib "Altium Content Vault") (part "777f9caa62b19d2ac513b26aa3e00a4"))
    )
    (comp (ref "U8")
      (value "OPA365AIDBVR")
      (footprint "DBV0005A_N")
      (fields (field (name "MANUFACTURER") "Texas Instruments") (field (name "JLCPCB PART NUMBER") "C96626"))
      (libsource (lib "Altium Content Vault") (part "TI-OPA364_5DBV5"))
    )
    (comp (ref "U9")
      (value "SN74LVC1G125DBVR")
      (footprint "DBV0005A_M")
      (description "Single Bus Buffer Gate With 3-State Outputs, DBV0005A, LARGE T&R")
      (fields
        (field (name "GENERIC PART NUMBER") "SN74LVC1G125")
        (field (name "MANUFACTURER") "Texas Instruments")
      )
      (libsource (lib "Altium Content Vault") (part "TI-SN74AXXXX1X125-5"))
    )
    (comp (ref "U10")
      (value "ADC121S101CIMF/NOPB")
      (footprint "MF06A_N")
      (description "Single Channel, 0.5 to 1 MSPS, 12-Bit A/D Converter, 6-pin SOT-23, Pb-Free")
      (fields
        (field (name "MANUFACTURER") "National Semiconductor")
        (field (name "JLCPCB PART NUMBER") "C74860")
      )
      (libsource (lib "Altium Content Vault") (part "CON-ADC-ADC101S101CIMF"))
    )
  )
  (nets
    (net (code "1") (name "/2V5_OUT") (class "Default")
      (node (ref "R3") (pin "1") (pinfunction "1_1") (pintype "passive"))
      (node (ref "R9") (pin "2") (pinfunction "2_2") (pintype "passive"))
      (node (ref "U3") (pin "1") (pinfunction "VOUT_1") (pintype "output"))
    )
    (net (code "2") (name "/5V_LDO") (class "Default")
      (node (ref "R38") (pin "1") (pinfunction "1_1") (pintype "passive"))
      (node (ref "U2") (pin "5") (pinfunction "OUT_5") (pintype "power_in"))
    )
    (net (code "3") (name "/5V_PG") (class "Default")
      (node (ref "R4") (pin "2") (pinfunction "2_2") (pintype "passive"))
      (node (ref "U1") (pin "6") (pinfunction "PG_6") (pintype "open_collector"))
      (node (ref "U2") (pin "3") (pinfunction "EN_3") (pintype "input"))
    )
    (net (code "4") (name "/AMP_OUT") (class "Default")
      (node (ref "C42") (pin "2") (pinfunction "2_2") (pintype "passive"))
      (node (ref "R31") (pin "1") (pinfunction "1_1") (pintype "passive"))
      (node (ref "R32") (pin "1") (pinfunction "1_1") (pintype "passive"))
      (node (ref "TP8") (pin "1") (pinfunction "1_1") (pintype "passive"))
      (node (ref "U8") (pin "1") (pinfunction "VOUT_1") (pintype "output"))
    )
    (net (code "5") (name "/BP_OUT") (class "Default")
      (node (ref "C33") (pin "2") (pinfunction "2_2") (pintype "passive"))
      (node (ref "C39") (pin "1") (pinfunction "1_1") (pintype "passive"))
      (node (ref "TP7") (pin "1") (pinfunction "1_1") (pintype "passive"))
      (node (ref "U5") (pin "13") (pinfunction "IN_D-_13") (pintype "input"))
      (node (ref "U5") (pin "14") (pinfunction "OUT_D_14") (pintype "output"))
    )
    (net (code "6") (name "/Buck_SW") (class "Default")
      (node (ref "L1") (pin "1") (pinfunction "1_1") (pintype "passive"))
      (node (ref "U1") (pin "7") (pinfunction "SW_7") (pintype "passive"))
    )
    (net (code "7") (name "/G") (class "Default")
      (node (ref "C24") (pin "1") (pinfunction "1_1") (pintype "passive"))
      (node (ref "R13") (pin "1") (pinfunction "1_1") (pintype "passive"))
      (node (ref "R15") (pin "1") (pinfunction "1_1") (pintype "passive"))
      (node (ref "R23") (pin "2") (pinfunction "2_2") (pintype "passive"))
      (node (ref "U6") (pin "2") (pinfunction "COM_2") (pintype "bidirectional"))
    )
    (net (code "8") (name "/GAIN_OUT") (class "Default")
      (node (ref "C24") (pin "2") (pinfunction "2_2") (pintype "passive"))
      (node (ref "C29") (pin "1") (pinfunction "1_1") (pintype "passive"))
      (node (ref "C35") (pin "1") (pinfunction "1_1") (pintype "passive"))
      (node (ref "R13") (pin "2") (pinfunction "2_2") (pintype "passive"))
      (node (ref "R26") (pin "1") (pinfunction "1_1") (pintype "passive"))
      (node (ref "TP5") (pin "1") (pinfunction "1_1") (pintype "passive"))
      (node (ref "U4") (pin "1") (pinfunction "VOUT_1") (pintype "output"))
    )
    (net (code "9") (name "/HYD+") (class "Default")
      (node (ref "J2") (pin "2") (pinfunction "2_2") (pintype "passive"))
      (node (ref "R14") (pin "1") (pinfunction "1_1") (pintype "passive"))
    )
    (net (code "10") (name "/I2C2_SCL") (class "Default")
      (node (ref "MD1") (pin "24") (pinfunction "TX6_24") (pintype "passive"))
      (node (ref "R8") (pin "1") (pinfunction "1_1") (pintype "passive"))
      (node (ref "U7") (pin "4") (pinfunction "SCL_4") (pintype "input"))
    )
    (net (code "11") (name "/I2C2_SDA") (class "Default")
      (node (ref "MD1") (pin "25") (pinfunction "RX6_25") (pintype "passive"))
      (node (ref "R6") (pin "1") (pinfunction "1_1") (pintype "passive"))
      (node (ref "U7") (pin "5") (pinfunction "SDA_5") (pintype "bidirectional"))
    )
    (net (code "12") (name "/LED_HB") (class "Default")
      (node (ref "MD1") (pin "8") (pinfunction "TX2_8") (pintype "passive"))
      (node (ref "R30") (pin "1") (pinfunction "1_1") (pintype "passive"))
    )
    (net (code "13") (name "/LED_TX") (class "Default")
      (node (ref "MD1") (pin "3") (pinfunction "LRCLK2_3") (pintype "passive"))
      (node (ref "R29") (pin "1") (pinfunction "1_1") (pintype "passive"))
    )
    (net (code "14") (name "/LNA_OUT") (class "Default")
      (node (ref "P2") (pin "1") (pinfunction "1_1") (pintype "passive"))
      (node (ref "Q1") (pin "1") (pinfunction "D_1") (pintype "passive"))
      (node (ref "R11") (pin "1") (pinfunction "1_1") (pintype "passive"))
      (node (ref "TP6") (pin "1") (pinfunction "1_1") (pintype "passive"))
    )
    (net (code "15") (name "/PA4_OUT") (class "Default")
      (node (ref "P2") (pin "3") (pinfunction "3_3") (pintype "passive"))
      (node (ref "R37") (pin "1") (pinfunction "1_1") (pintype "passive"))
    )
    (net (code "16") (name "/POT_A") (class "Default")
      (node (ref "R36") (pin "2") (pinfunction "2_2") (pintype "passive"))
      (node (ref "U7") (pin "8") (pinfunction "A_8") (pintype "passive"))
    )
    (net (code "17") (name "/POT_B") (class "Default")
      (node (ref "R31") (pin "2") (pinfunction "2_2") (pintype "passive"))
      (node (ref "U7") (pin "7") (pinfunction "B_7") (pintype "passive"))
    )
    (net (code "18") (name "/POT_W") (class "Default")
      (node (ref "C42") (pin "1") (pinfunction "1_1") (pintype "passive"))
      (node (ref "R35") (pin "2") (pinfunction "2_2") (pintype "passive"))
      (node (ref "U7") (pin "1") (pinfunction "W_1") (pintype "passive"))
    )
    (net (code "19") (name "/PRE_OUT") (class "Default")
      (node (ref "C19") (pin "1") (pinfunction "1_1") (pintype "passive"))
      (node (ref "P2") (pin "2") (pinfunction "2_2") (pintype "passive"))
    )
    (net (code "20") (name "/RX_GAIN_SEL") (class "Default")
      (node (ref "MD1") (pin "10") (pinfunction "CS_10") (pintype "passive"))
      (node (ref "R27") (pin "2") (pinfunction "2_2") (pintype "passive"))
    )
    (net (code "21") (name "/SPI1_CS") (class "Default")
      (node (ref "MD1") (pin "28") (pinfunction "RX7_28") (pintype "passive"))
      (node (ref "U10") (pin "6") (pinfunction "~{CS}_6") (pintype "input"))
      (node (ref "U9") (pin "1") (pinfunction "~{OE}_1") (pintype "input"))
    )
    (net (code "22") (name "/SPI1_MISO") (class "Default")
      (node (ref "MD1") (pin "39") (pinfunction "MISO1_39") (pintype "passive"))
      (node (ref "U9") (pin "4") (pinfunction "Y_4") (pintype "tri_state"))
    )
    (net (code "23") (name "/SPI1_SCK") (class "Default")
      (node (ref "MD1") (pin "27") (pinfunction "SCK1_27") (pintype "passive"))
      (node (ref "U10") (pin "4") (pinfunction "SCLK_4") (pintype "input"))
    )
    (net (code "24") (name "/VIN_Supply") (class "Default")
      (node (ref "D1") (pin "A") (pinfunction "A_A") (pintype "passive"))
      (node (ref "J1") (pin "2") (pinfunction "2_2") (pintype "passive"))
    )
    (net (code "25") (name "2V5") (class "Default")
      (node (ref "C13") (pin "1") (pinfunction "1_1") (pintype "passive"))
      (node (ref "C14") (pin "2") (pinfunction "2_2") (pintype "passive"))
      (node (ref "C25") (pin "2") (pinfunction "2_2") (pintype "passive"))
      (node (ref "C34") (pin "2") (pinfunction "2_2") (pintype "passive"))
      (node (ref "C46") (pin "2") (pinfunction "2_2") (pintype "passive"))
      (node (ref "C48") (pin "2") (pinfunction "2_2") (pintype "passive"))
      (node (ref "R12") (pin "1") (pinfunction "1_1") (pintype "passive"))
      (node (ref "R21") (pin "1") (pinfunction "1_1") (pintype "passive"))
      (node (ref "R23") (pin "1") (pinfunction "1_1") (pintype "passive"))
      (node (ref "R24") (pin "1") (pinfunction "1_1") (pintype "passive"))
      (node (ref "R3") (pin "2") (pinfunction "2_2") (pintype "passive"))
      (node (ref "R34") (pin "2") (pinfunction "2_2") (pintype "passive"))
      (node (ref "R36") (pin "1") (pinfunction "1_1") (pintype "passive"))
      (node (ref "TP4") (pin "1") (pinfunction "1_1") (pintype "passive"))
    )
    (net (code "26") (name "5V") (class "Default")
      (node (ref "C15") (pin "2") (pinfunction "2_2") (pintype "passive"))
      (node (ref "C16") (pin "1") (pinfunction "1_1") (pintype "passive"))
      (node (ref "C17") (pin "2") (pinfunction "2_2") (pintype "passive"))
      (node (ref "C18") (pin "2") (pinfunction "2_2") (pintype "passive"))
      (node (ref "C2") (pin "2") (pinfunction "2_2") (pintype "passive"))
      (node (ref "C20") (pin "1") (pinfunction "1_1") (pintype "passive"))
      (node (ref "C21") (pin "2") (pinfunction "2_2") (pintype "passive"))
      (node (ref "C3") (pin "1") (pinfunction "1_1") (pintype "passive"))
      (node (ref "C36") (pin "2") (pinfunction "2_2") (pintype "passive"))
      (node (ref "C37") (pin "2") (pinfunction "2_2") (pintype "passive"))
      (node (ref "C38") (pin "2") (pinfunction "2_2") (pintype "passive"))
      (node (ref "C40") (pin "1") (pinfunction "1_1") (pintype "passive"))
      (node (ref "C41") (pin "2") (pinfunction "2_2") (pintype "passive"))
      (node (ref "C44") (pin "2") (pinfunction "2_2") (pintype "passive"))
      (node (ref "C45") (pin "2") (pinfunction "2_2") (pintype "passive"))
      (node (ref "P3") (pin "2") (pinfunction "2_2") (pintype "passive"))
      (node (ref "R10") (pin "1") (pinfunction "1_1") (pintype "passive"))
      (node (ref "R2") (pin "2") (pinfunction "2_2") (pintype "passive"))
      (node (ref "R33") (pin "1") (pinfunction "1_1") (pintype "passive"))
      (node (ref "R38") (pin "2") (pinfunction "2_2") (pintype "passive"))
      (node (ref "TP2") (pin "1") (pinfunction "1_1") (pintype "passive"))
      (node (ref "U10") (pin "1") (pinfunction "VA_1") (pintype "power_in"))
      (node (ref "U3") (pin "5") (pinfunction "+VS_5") (pintype "power_in"))
      (node (ref "U4") (pin "5") (pinfunction "~{DISABLE}_5") (pintype "input"))
      (node (ref "U4") (pin "6") (pinfunction "+VS_6") (pintype "power_in"))
      (node (ref "U5") (pin "4") (pinfunction "V+_4") (pintype "power_in"))
      (node (ref "U6") (pin "5") (pinfunction "V+_5") (pintype "power_in"))
      (node (ref "U7") (pin "2") (pinfunction "VDD_2") (pintype "power_in"))
      (node (ref "U8") (pin "5") (pinfunction "V+_5") (pintype "power_in"))
    )
    (net (code "27") (name "5V25") (class "Default")
      (node (ref "C1") (pin "2") (pinfunction "2_2") (pintype "passive"))
      (node (ref "C10") (pin "2") (pinfunction "2_2") (pintype "passive"))
      (node (ref "C6") (pin "1") (pinfunction "1_1") (pintype "passive"))
      (node (ref "C7") (pin "2") (pinfunction "2_2") (pintype "passive"))
      (node (ref "L1") (pin "2") (pinfunction "2_2") (pintype "passive"))
      (node (ref "R1") (pin "2") (pinfunction "2_2") (pintype "passive"))
      (node (ref "R4") (pin "1") (pinfunction "1_1") (pintype "passive"))
      (node (ref "TP1") (pin "1") (pinfunction "1_1") (pintype "passive"))
      (node (ref "U1") (pin "8") (pinfunction "VOUT_8") (pintype "power_in"))
      (node (ref "U2") (pin "1") (pinfunction "IN_1") (pintype "power_in"))
    )
    (net (code "28") (name "GND") (class "Default")
      (node (ref "C10") (pin "1") (pinfunction "1_1") (pintype "passive"))
      (node (ref "C11") (pin "1") (pinfunction "1_1") (pintype "passive"))
      (node (ref "C12") (pin "2") (pinfunction "2_2") (pintype "passive"))
      (node (ref "C13") (pin "2") (pinfunction "2_2") (pintype "passive"))
      (node (ref "C14") (pin "1") (pinfunction "1_1") (pintype "passive"))
      (node (ref "C15") (pin "1") (pinfunction "1_1") (pintype "passive"))
      (node (ref "C16") (pin "2") (pinfunction "2_2") (pintype "passive"))
      (node (ref "C17") (pin "1") (pinfunction "1_1") (pintype "passive"))
      (node (ref "C18") (pin "1") (pinfunction "1_1") (pintype "passive"))
      (node (ref "C2") (pin "1") (pinfunction "1_1") (pintype "passive"))
      (node (ref "C20") (pin "2") (pinfunction "2_2") (pintype "passive"))
      (node (ref "C21") (pin "1") (pinfunction "1_1") (pintype "passive"))
      (node (ref "C22") (pin "1") (pinfunction "1_1") (pintype "passive"))
      (node (ref "C23") (pin "1") (pinfunction "1_1") (pintype "passive"))
      (node (ref "C25") (pin "1") (pinfunction "1_1") (pintype "passive"))
      (node (ref "C28") (pin "1") (pinfunction "1_1") (pintype "passive"))
      (node (ref "C3") (pin "2") (pinfunction "2_2") (pintype "passive"))
      (node (ref "C31") (pin "1") (pinfunction "1_1") (pintype "passive"))
      (node (ref "C34") (pin "1") (pinfunction "1_1") (pintype "passive"))
      (node (ref "C36") (pin "1") (pinfunction "1_1") (pintype "passive"))
      (node (ref "C37") (pin "1") (pinfunction "1_1") (pintype "passive"))
      (node (ref "C38") (pin "1") (pinfunction "1_1") (pintype "passive"))
      (node (ref "C4") (pin "1") (pinfunction "1_1") (pintype "passive"))
      (node (ref "C40") (pin "2") (pinfunction "2_2") (pintype "passive"))
      (node (ref "C41") (pin "1") (pinfunction "1_1") (pintype "passive"))
      (node (ref "C43") (pin "1") (pinfunction "1_1") (pintype "passive"))
      (node (ref "C44") (pin "1") (pinfunction "1_1") (pintype "passive"))
      (node (ref "C45") (pin "1") (pinfunction "1_1") (pintype "passive"))
      (node (ref "C46") (pin "1") (pinfunction "1_1") (pintype "passive"))
      (node (ref "C47") (pin "1") (pinfunction "1_1") (pintype "passive"))
      (node (ref "C48") (pin "1") (pinfunction "1_1") (pintype "passive"))
      (node (ref "C5") (pin "2") (pinfunction "-_2") (pintype "passive"))
      (node (ref "C6") (pin "2") (pinfunction "2_2") (pintype "passive"))
      (node (ref "C7") (pin "1") (pinfunction "1_1") (pintype "passive"))
      (node (ref "C8") (pin "1") (pinfunction "1_1") (pintype "passive"))
      (node (ref "C9") (pin "1") (pinfunction "1_1") (pintype "passive"))
      (node (ref "D2") (pin "2") (pinfunction "A_2") (pintype "passive"))
      (node (ref "D3") (pin "3") (pinfunction "3_3") (pintype "passive"))
      (node (ref "D4") (pin "1") (pinfunction "C_1") (pintype "passive"))
      (node (ref "D5") (pin "1") (pinfunction "C_1") (pintype "passive"))
      (node (ref "D6") (pin "1") (pinfunction "C_1") (pintype "passive"))
      (node (ref "J1") (pin "1") (pinfunction "1_1") (pintype "passive"))
      (node (ref "J2") (pin "1") (pinfunction "1_1") (pintype "passive"))
      (node (ref "MD1") (pin "43") (pinfunction "GND_43") (pintype "passive"))
      (node (ref "MD1") (pin "45") (pinfunction "GND_45") (pintype "passive"))
      (node (ref "MD1") (pin "46") (pinfunction "GND_46") (pintype "passive"))
      (node (ref "P1") (pin "3") (pinfunction "3_3") (pintype "passive"))
      (node (ref "P3") (pin "1") (pinfunction "1_1") (pintype "passive"))
      (node (ref "Q1") (pin "2") (pinfunction "S_2") (pintype "passive"))
      (node (ref "R20") (pin "1") (pinfunction "1_1") (pintype "passive"))
      (node (ref "R28") (pin "1") (pinfunction "1_1") (pintype "passive"))
      (node (ref "R5") (pin "1") (pinfunction "1_1") (pintype "passive"))
      (node (ref "R7") (pin "2") (pinfunction "2_2") (pintype "passive"))
      (node (ref "U1") (pin "2") (pinfunction "GND_2") (pintype "power_in"))
      (node (ref "U10") (pin "2") (pinfunction "GND_2") (pintype "power_in"))
      (node (ref "U2") (pin "2") (pinfunction "GND_2") (pintype "power_in"))
      (node (ref "U3") (pin "2") (pinfunction "-VS_2") (pintype "power_in"))
      (node (ref "U4") (pin "2") (pinfunction "-VS_2") (pintype "power_in"))
      (node (ref "U5") (pin "11") (pinfunction "V-_11") (pintype "power_in"))
      (node (ref "U6") (pin "3") (pinfunction "GND_3") (pintype "power_in"))
      (node (ref "U7") (pin "3") (pinfunction "GND_3") (pintype "power_in"))
      (node (ref "U7") (pin "6") (pinfunction "AD0_6") (pintype "input"))
      (node (ref "U8") (pin "2") (pinfunction "V-_2") (pintype "power_in"))
      (node (ref "U9") (pin "3") (pinfunction "GND_3") (pintype "power_in"))
    )
    (net (code "29") (name "Net-(C22-Pad2)") (class "Default")
      (node (ref "C22") (pin "2") (pinfunction "2_2") (pintype "passive"))
      (node (ref "C23") (pin "2") (pinfunction "2_2") (pintype "passive"))
      (node (ref "R10") (pin "2") (pinfunction "2_2") (pintype "passive"))
      (node (ref "R11") (pin "2") (pinfunction "2_2") (pintype "passive"))
    )
    (net (code "30") (name "Net-(C26-Pad2)") (class "Default")
      (node (ref "C26") (pin "2") (pinfunction "2_2") (pintype "passive"))
      (node (ref "C27") (pin "1") (pinfunction "1_1") (pintype "passive"))
      (node (ref "R22") (pin "1") (pinfunction "1_1") (pintype "passive"))
    )
    (net (code "31") (name "Net-(C29-Pad2)") (class "Default")
      (node (ref "C29") (pin "2") (pinfunction "2_2") (pintype "passive"))
      (node (ref "C30") (pin "1") (pinfunction "1_1") (pintype "passive"))
      (node (ref "R25") (pin "1") (pinfunction "1_1") (pintype "passive"))
    )
    (net (code "32") (name "Net-(C32-Pad1)") (class "Default")
      (node (ref "C32") (pin "1") (pinfunction "1_1") (pintype "passive"))
      (node (ref "R18") (pin "2") (pinfunction "2_2") (pintype "passive"))
      (node (ref "R19") (pin "1") (pinfunction "1_1") (pintype "passive"))
    )
    (net (code "33") (name "Net-(C33-Pad1)") (class "Default")
      (node (ref "C33") (pin "1") (pinfunction "1_1") (pintype "passive"))
      (node (ref "R16") (pin "2") (pinfunction "2_2") (pintype "passive"))
      (node (ref "R17") (pin "1") (pinfunction "1_1") (pintype "passive"))
    )
    (net (code "34") (name "Net-(D4-A)") (class "Default")
      (node (ref "D4") (pin "2") (pinfunction "A_2") (pintype "passive"))
      (node (ref "R29") (pin "2") (pinfunction "2_2") (pintype "passive"))
    )
    (net (code "35") (name "Net-(D5-A)") (class "Default")
      (node (ref "D5") (pin "2") (pinfunction "A_2") (pintype "passive"))
      (node (ref "R30") (pin "2") (pinfunction "2_2") (pintype "passive"))
    )
    (net (code "36") (name "Net-(D6-A)") (class "Default")
      (node (ref "D6") (pin "2") (pinfunction "A_2") (pintype "passive"))
      (node (ref "R33") (pin "2") (pinfunction "2_2") (pintype "passive"))
    )
    (net (code "37") (name "Net-(P1-Pad2)") (class "Default")
      (node (ref "P1") (pin "2") (pinfunction "2_2") (pintype "passive"))
      (node (ref "R37") (pin "2") (pinfunction "2_2") (pintype "passive"))
    )
    (net (code "38") (name "Net-(Q1-G)") (class "Default")
      (node (ref "D3") (pin "1") (pinfunction "1_1") (pintype "passive"))
      (node (ref "D3") (pin "2") (pinfunction "2_2") (pintype "passive"))
      (node (ref "Q1") (pin "3") (pinfunction "G_3") (pintype "passive"))
      (node (ref "R14") (pin "2") (pinfunction "2_2") (pintype "passive"))
      (node (ref "R20") (pin "2") (pinfunction "2_2") (pintype "passive"))
    )
    (net (code "39") (name "Net-(U1-FB)") (class "Default")
      (node (ref "C1") (pin "1") (pinfunction "1_1") (pintype "passive"))
      (node (ref "R1") (pin "1") (pinfunction "1_1") (pintype "passive"))
      (node (ref "R5") (pin "2") (pinfunction "2_2") (pintype "passive"))
      (node (ref "U1") (pin "5") (pinfunction "FB_5") (pintype "passive"))
    )
    (net (code "40") (name "Net-(U2-NR)") (class "Default")
      (node (ref "C4") (pin "2") (pinfunction "2_2") (pintype "passive"))
      (node (ref "U2") (pin "4") (pinfunction "NR_4") (pintype "passive"))
    )
    (net (code "41") (name "Net-(U3-+IN)") (class "Default")
      (node (ref "C11") (pin "2") (pinfunction "2_2") (pintype "passive"))
      (node (ref "C12") (pin "1") (pinfunction "1_1") (pintype "passive"))
      (node (ref "R2") (pin "1") (pinfunction "1_1") (pintype "passive"))
      (node (ref "R7") (pin "1") (pinfunction "1_1") (pintype "passive"))
      (node (ref "U3") (pin "3") (pinfunction "+IN_3") (pintype "input"))
    )
    (net (code "42") (name "Net-(U3--IN)") (class "Default")
      (node (ref "R9") (pin "1") (pinfunction "1_1") (pintype "passive"))
      (node (ref "U3") (pin "4") (pinfunction "-IN_4") (pintype "input"))
    )
    (net (code "43") (name "Net-(U4-+IN)") (class "Default")
      (node (ref "C19") (pin "2") (pinfunction "2_2") (pintype "passive"))
      (node (ref "R12") (pin "2") (pinfunction "2_2") (pintype "passive"))
      (node (ref "U4") (pin "3") (pinfunction "+IN_3") (pintype "tri_state"))
    )
    (net (code "44") (name "Net-(U4--IN)") (class "Default")
      (node (ref "R15") (pin "2") (pinfunction "2_2") (pintype "passive"))
      (node (ref "U4") (pin "4") (pinfunction "-IN_4") (pintype "tri_state"))
    )
    (net (code "45") (name "Net-(U5A-IN_A+)") (class "Default")
      (node (ref "C30") (pin "2") (pinfunction "2_2") (pintype "passive"))
      (node (ref "R24") (pin "2") (pinfunction "2_2") (pintype "passive"))
      (node (ref "U5") (pin "3") (pinfunction "IN_A+_3") (pintype "input"))
    )
    (net (code "46") (name "Net-(U5A-IN_A-)") (class "Default")
      (node (ref "C26") (pin "1") (pinfunction "1_1") (pintype "passive"))
      (node (ref "R25") (pin "2") (pinfunction "2_2") (pintype "passive"))
      (node (ref "U5") (pin "1") (pinfunction "OUT_A_1") (pintype "output"))
      (node (ref "U5") (pin "2") (pinfunction "IN_A-_2") (pintype "input"))
    )
    (net (code "47") (name "Net-(U5B-IN_B+)") (class "Default")
      (node (ref "C27") (pin "2") (pinfunction "2_2") (pintype "passive"))
      (node (ref "R21") (pin "2") (pinfunction "2_2") (pintype "passive"))
      (node (ref "U5") (pin "5") (pinfunction "IN_B+_5") (pintype "input"))
    )
    (net (code "48") (name "Net-(U5B-IN_B-)") (class "Default")
      (node (ref "R18") (pin "1") (pinfunction "1_1") (pintype "passive"))
      (node (ref "R22") (pin "2") (pinfunction "2_2") (pintype "passive"))
      (node (ref "U5") (pin "6") (pinfunction "IN_B-_6") (pintype "input"))
      (node (ref "U5") (pin "7") (pinfunction "OUT_B_7") (pintype "output"))
    )
    (net (code "49") (name "Net-(U5C-IN_C+)") (class "Default")
      (node (ref "C31") (pin "2") (pinfunction "2_2") (pintype "passive"))
      (node (ref "R19") (pin "2") (pinfunction "2_2") (pintype "passive"))
      (node (ref "U5") (pin "10") (pinfunction "IN_C+_10") (pintype "input"))
    )
    (net (code "50") (name "Net-(U5C-IN_C-)") (class "Default")
      (node (ref "C32") (pin "2") (pinfunction "2_2") (pintype "passive"))
      (node (ref "R16") (pin "1") (pinfunction "1_1") (pintype "passive"))
      (node (ref "U5") (pin "8") (pinfunction "OUT_C_8") (pintype "output"))
      (node (ref "U5") (pin "9") (pinfunction "IN_C-_9") (pintype "input"))
    )
    (net (code "51") (name "Net-(U5D-IN_D+)") (class "Default")
      (node (ref "C28") (pin "2") (pinfunction "2_2") (pintype "passive"))
      (node (ref "R17") (pin "2") (pinfunction "2_2") (pintype "passive"))
      (node (ref "U5") (pin "12") (pinfunction "IN_D+_12") (pintype "input"))
    )
    (net (code "52") (name "Net-(U6-IN)") (class "Default")
      (node (ref "R27") (pin "1") (pinfunction "1_1") (pintype "passive"))
      (node (ref "R28") (pin "2") (pinfunction "2_2") (pintype "passive"))
      (node (ref "U6") (pin "4") (pinfunction "IN_4") (pintype "input"))
    )
    (net (code "53") (name "Net-(U6-NO)") (class "Default")
      (node (ref "C35") (pin "2") (pinfunction "2_2") (pintype "passive"))
      (node (ref "R26") (pin "2") (pinfunction "2_2") (pintype "passive"))
      (node (ref "U6") (pin "1") (pinfunction "NO_1") (pintype "bidirectional"))
    )
    (net (code "54") (name "Net-(U8-IN+)") (class "Default")
      (node (ref "C39") (pin "2") (pinfunction "2_2") (pintype "passive"))
      (node (ref "R34") (pin "1") (pinfunction "1_1") (pintype "passive"))
      (node (ref "U8") (pin "3") (pinfunction "IN+_3") (pintype "input"))
    )
    (net (code "55") (name "Net-(U8-IN-)") (class "Default")
      (node (ref "R35") (pin "1") (pinfunction "1_1") (pintype "passive"))
      (node (ref "U8") (pin "4") (pinfunction "IN-_4") (pintype "input"))
    )
    (net (code "56") (name "Net-(U10-SDATA)") (class "Default")
      (node (ref "U10") (pin "5") (pinfunction "SDATA_5") (pintype "output"))
      (node (ref "U9") (pin "2") (pinfunction "A_2") (pintype "input"))
    )
    (net (code "57") (name "Net-(U10-VIN)") (class "Default")
      (node (ref "C43") (pin "2") (pinfunction "2_2") (pintype "passive"))
      (node (ref "R32") (pin "2") (pinfunction "2_2") (pintype "passive"))
      (node (ref "U10") (pin "3") (pinfunction "VIN_3") (pintype "input"))
    )
    (net (code "58") (name "Teensy_3V3") (class "Default")
      (node (ref "C47") (pin "2") (pinfunction "2_2") (pintype "passive"))
      (node (ref "MD1") (pin "47") (pinfunction "3.3V_47") (pintype "passive"))
      (node (ref "R6") (pin "2") (pinfunction "2_2") (pintype "passive"))
      (node (ref "R8") (pin "2") (pinfunction "2_2") (pintype "passive"))
      (node (ref "U9") (pin "5") (pinfunction "VCC_5") (pintype "power_in"))
    )
    (net (code "59") (name "VIN") (class "Default")
      (node (ref "C5") (pin "1") (pinfunction "+_1") (pintype "passive"))
      (node (ref "C8") (pin "2") (pinfunction "2_2") (pintype "passive"))
      (node (ref "C9") (pin "2") (pinfunction "2_2") (pintype "passive"))
      (node (ref "D1") (pin "K") (pinfunction "K_K") (pintype "passive"))
      (node (ref "D2") (pin "1") (pinfunction "K_1") (pintype "passive"))
      (node (ref "P1") (pin "1") (pinfunction "1_1") (pintype "passive"))
      (node (ref "TP3") (pin "1") (pinfunction "1_1") (pintype "passive"))
      (node (ref "U1") (pin "1") (pinfunction "VIN_1") (pintype "power_in"))
      (node (ref "U1") (pin "3") (pinfunction "EN_3") (pintype "input"))
    )
    (net (code "60") (name "unconnected-(MD1-3.3V-Pad44)") (class "Default")
      (node (ref "MD1") (pin "44") (pinfunction "3.3V_44") (pintype "passive"))
    )
    (net (code "61") (name "unconnected-(MD1-A16-Pad40)") (class "Default")
      (node (ref "MD1") (pin "40") (pinfunction "A16_40") (pintype "passive"))
    )
    (net (code "62") (name "unconnected-(MD1-A17-Pad41)") (class "Default")
      (node (ref "MD1") (pin "41") (pinfunction "A17_41") (pintype "passive"))
    )
    (net (code "63") (name "unconnected-(MD1-BCLK2-Pad4)") (class "Default")
      (node (ref "MD1") (pin "4") (pinfunction "BCLK2_4") (pintype "passive"))
    )
    (net (code "64") (name "unconnected-(MD1-CRX1-Pad23)") (class "Default")
      (node (ref "MD1") (pin "23") (pinfunction "CRX1_23") (pintype "passive"))
    )
    (net (code "65") (name "unconnected-(MD1-CRX3-Pad30)") (class "Default")
      (node (ref "MD1") (pin "30") (pinfunction "CRX3_30") (pintype "passive"))
    )
    (net (code "66") (name "unconnected-(MD1-CS-Pad36)") (class "Default")
      (node (ref "MD1") (pin "36") (pinfunction "CS_36") (pintype "passive"))
    )
    (net (code "67") (name "unconnected-(MD1-CS-Pad37)") (class "Default")
      (node (ref "MD1") (pin "37") (pinfunction "CS_37") (pintype "passive"))
    )
    (net (code "68") (name "unconnected-(MD1-CS1-Pad38)") (class "Default")
      (node (ref "MD1") (pin "38") (pinfunction "CS1_38") (pintype "passive"))
    )
    (net (code "69") (name "unconnected-(MD1-CTX1-Pad22)") (class "Default")
      (node (ref "MD1") (pin "22") (pinfunction "CTX1_22") (pintype "passive"))
    )
    (net (code "70") (name "unconnected-(MD1-CTX3-Pad31)") (class "Default")
      (node (ref "MD1") (pin "31") (pinfunction "CTX3_31") (pintype "passive"))
    )
    (net (code "71") (name "unconnected-(MD1-IN2-Pad5)") (class "Default")
      (node (ref "MD1") (pin "5") (pinfunction "IN2_5") (pintype "passive"))
    )
    (net (code "72") (name "unconnected-(MD1-MCLK2-Pad33)") (class "Default")
      (node (ref "MD1") (pin "33") (pinfunction "MCLK2_33") (pintype "passive"))
    )
    (net (code "73") (name "unconnected-(MD1-MISO-Pad12)") (class "Default")
      (node (ref "MD1") (pin "12") (pinfunction "MISO_12") (pintype "passive"))
    )
    (net (code "74") (name "unconnected-(MD1-MOSI-Pad11)") (class "Default")
      (node (ref "MD1") (pin "11") (pinfunction "MOSI_11") (pintype "passive"))
    )
    (net (code "75") (name "unconnected-(MD1-MOSI1-Pad26)") (class "Default")
      (node (ref "MD1") (pin "26") (pinfunction "MOSI1_26") (pintype "passive"))
    )
    (net (code "76") (name "unconnected-(MD1-OUT1B-Pad32)") (class "Default")
      (node (ref "MD1") (pin "32") (pinfunction "OUT1B_32") (pintype "passive"))
    )
    (net (code "77") (name "unconnected-(MD1-OUT1C-Pad9)") (class "Default")
      (node (ref "MD1") (pin "9") (pinfunction "OUT1C_9") (pintype "passive"))
    )
    (net (code "78") (name "unconnected-(MD1-OUT1D-Pad6)") (class "Default")
      (node (ref "MD1") (pin "6") (pinfunction "OUT1D_6") (pintype "passive"))
    )
    (net (code "79") (name "unconnected-(MD1-OUT2-Pad2)") (class "Default")
      (node (ref "MD1") (pin "2") (pinfunction "OUT2_2") (pintype "passive"))
    )
    (net (code "80") (name "unconnected-(MD1-RX1-Pad0)") (class "Default")
      (node (ref "MD1") (pin "0") (pinfunction "RX1_0") (pintype "passive"))
    )
    (net (code "81") (name "unconnected-(MD1-RX2-Pad7)") (class "Default")
      (node (ref "MD1") (pin "7") (pinfunction "RX2_7") (pintype "passive"))
    )
    (net (code "82") (name "unconnected-(MD1-RX3-Pad15)") (class "Default")
      (node (ref "MD1") (pin "15") (pinfunction "RX3_15") (pintype "passive"))
    )
    (net (code "83") (name "unconnected-(MD1-RX4-Pad16)") (class "Default")
      (node (ref "MD1") (pin "16") (pinfunction "RX4_16") (pintype "passive"))
    )
    (net (code "84") (name "unconnected-(MD1-RX5-Pad21)") (class "Default")
      (node (ref "MD1") (pin "21") (pinfunction "RX5_21") (pintype "passive"))
    )
    (net (code "85") (name "unconnected-(MD1-RX8-Pad34)") (class "Default")
      (node (ref "MD1") (pin "34") (pinfunction "RX8_34") (pintype "passive"))
    )
    (net (code "86") (name "unconnected-(MD1-SCL-Pad19)") (class "Default")
      (node (ref "MD1") (pin "19") (pinfunction "SCL_19") (pintype "passive"))
    )
    (net (code "87") (name "unconnected-(MD1-SCLK-Pad13)") (class "Default")
      (node (ref "MD1") (pin "13") (pinfunction "SCLK_13") (pintype "passive"))
    )
    (net (code "88") (name "unconnected-(MD1-SDA-Pad18)") (class "Default")
      (node (ref "MD1") (pin "18") (pinfunction "SDA_18") (pintype "passive"))
    )
    (net (code "89") (name "unconnected-(MD1-TX1-Pad1)") (class "Default")
      (node (ref "MD1") (pin "1") (pinfunction "TX1_1") (pintype "passive"))
    )
    (net (code "90") (name "unconnected-(MD1-TX3-Pad14)") (class "Default")
      (node (ref "MD1") (pin "14") (pinfunction "TX3_14") (pintype "passive"))
    )
    (net (code "91") (name "unconnected-(MD1-TX4-Pad17)") (class "Default")
      (node (ref "MD1") (pin "17") (pinfunction "TX4_17") (pintype "passive"))
    )
    (net (code "92") (name "unconnected-(MD1-TX5-Pad20)") (class "Default")
      (node (ref "MD1") (pin "20") (pinfunction "TX5_20") (pintype "passive"))
    )
    (net (code "93") (name "unconnected-(MD1-TX7-Pad29)") (class "Default")
      (node (ref "MD1") (pin "29") (pinfunction "TX7_29") (pintype "passive"))
    )
    (net (code "94") (name "unconnected-(MD1-TX8-Pad35)") (class "Default")
      (node (ref "MD1") (pin "35") (pinfunction "TX8_35") (pintype "passive"))
    )
    (net (code "95") (name "unconnected-(MD1-VIN-Pad42)") (class "Default")
      (node (ref "MD1") (pin "42") (pinfunction "VIN_42") (pintype "passive"))
    )
    (net (code "96") (name "unconnected-(U1-SGND-Pad4)") (class "Default")
      (node (ref "U1") (pin "4") (pinfunction "SGND_4") (pintype "power_in+no_connect"))
    )
    (net (code "97") (name "unconnected-(U5B-V+-Pad4)") (class "Default")
      (node (ref "U5") (pin "4") (pinfunction "V+_4") (pintype "power_in+no_connect"))
    )
    (net (code "98") (name "unconnected-(U5B-V--Pad11)") (class "Default")
      (node (ref "U5") (pin "11") (pinfunction "V-_11") (pintype "power_in+no_connect"))
    )
    (net (code "99") (name "unconnected-(U5C-V+-Pad4)") (class "Default")
      (node (ref "U5") (pin "4") (pinfunction "V+_4") (pintype "power_in+no_connect"))
    )
    (net (code "100") (name "unconnected-(U5C-V--Pad11)") (class "Default")
      (node (ref "U5") (pin "11") (pinfunction "V-_11") (pintype "power_in+no_connect"))
    )
    (net (code "101") (name "unconnected-(U5D-V+-Pad4)") (class "Default")
      (node (ref "U5") (pin "4") (pinfunction "V+_4") (pintype "power_in+no_connect"))
    )
    (net (code "102") (name "unconnected-(U5D-V--Pad11)") (class "Default")
      (node (ref "U5") (pin "11") (pinfunction "V-_11") (pintype "power_in+no_connect"))
    )
  )
)
